# control_board.net
KiCad netlist of a schematic drawn in EAGLE
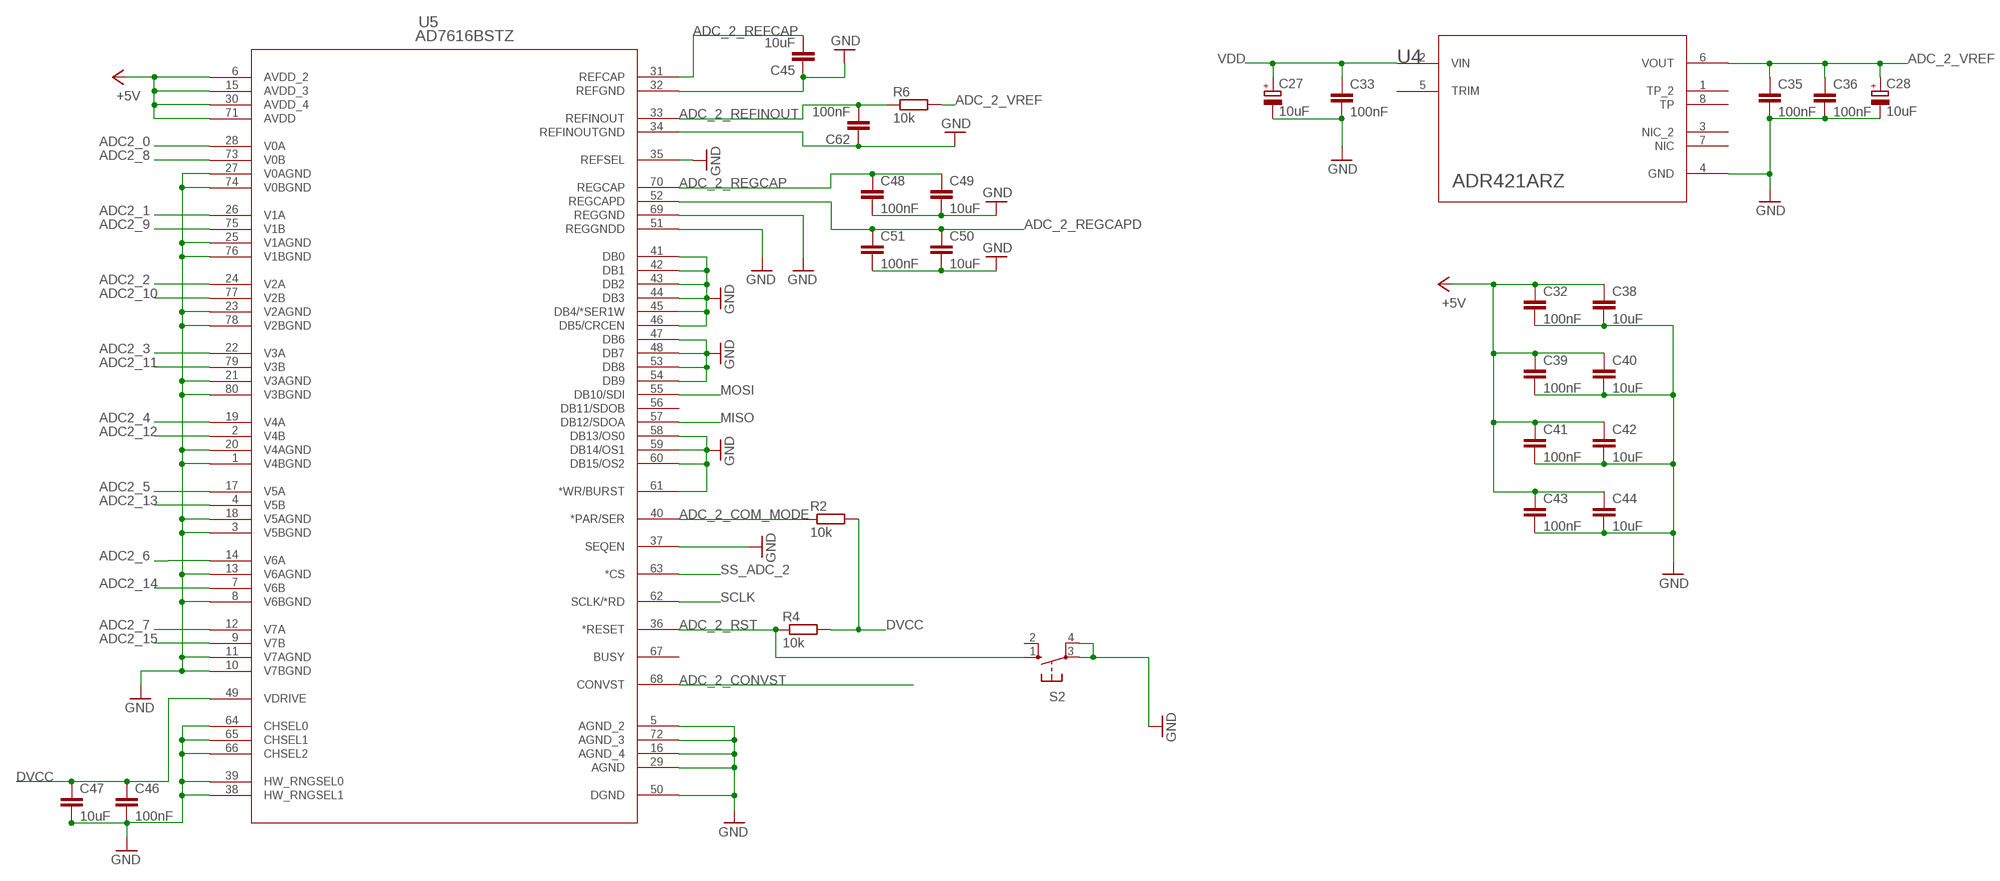
[diagram p0: schematic, sheet 1]
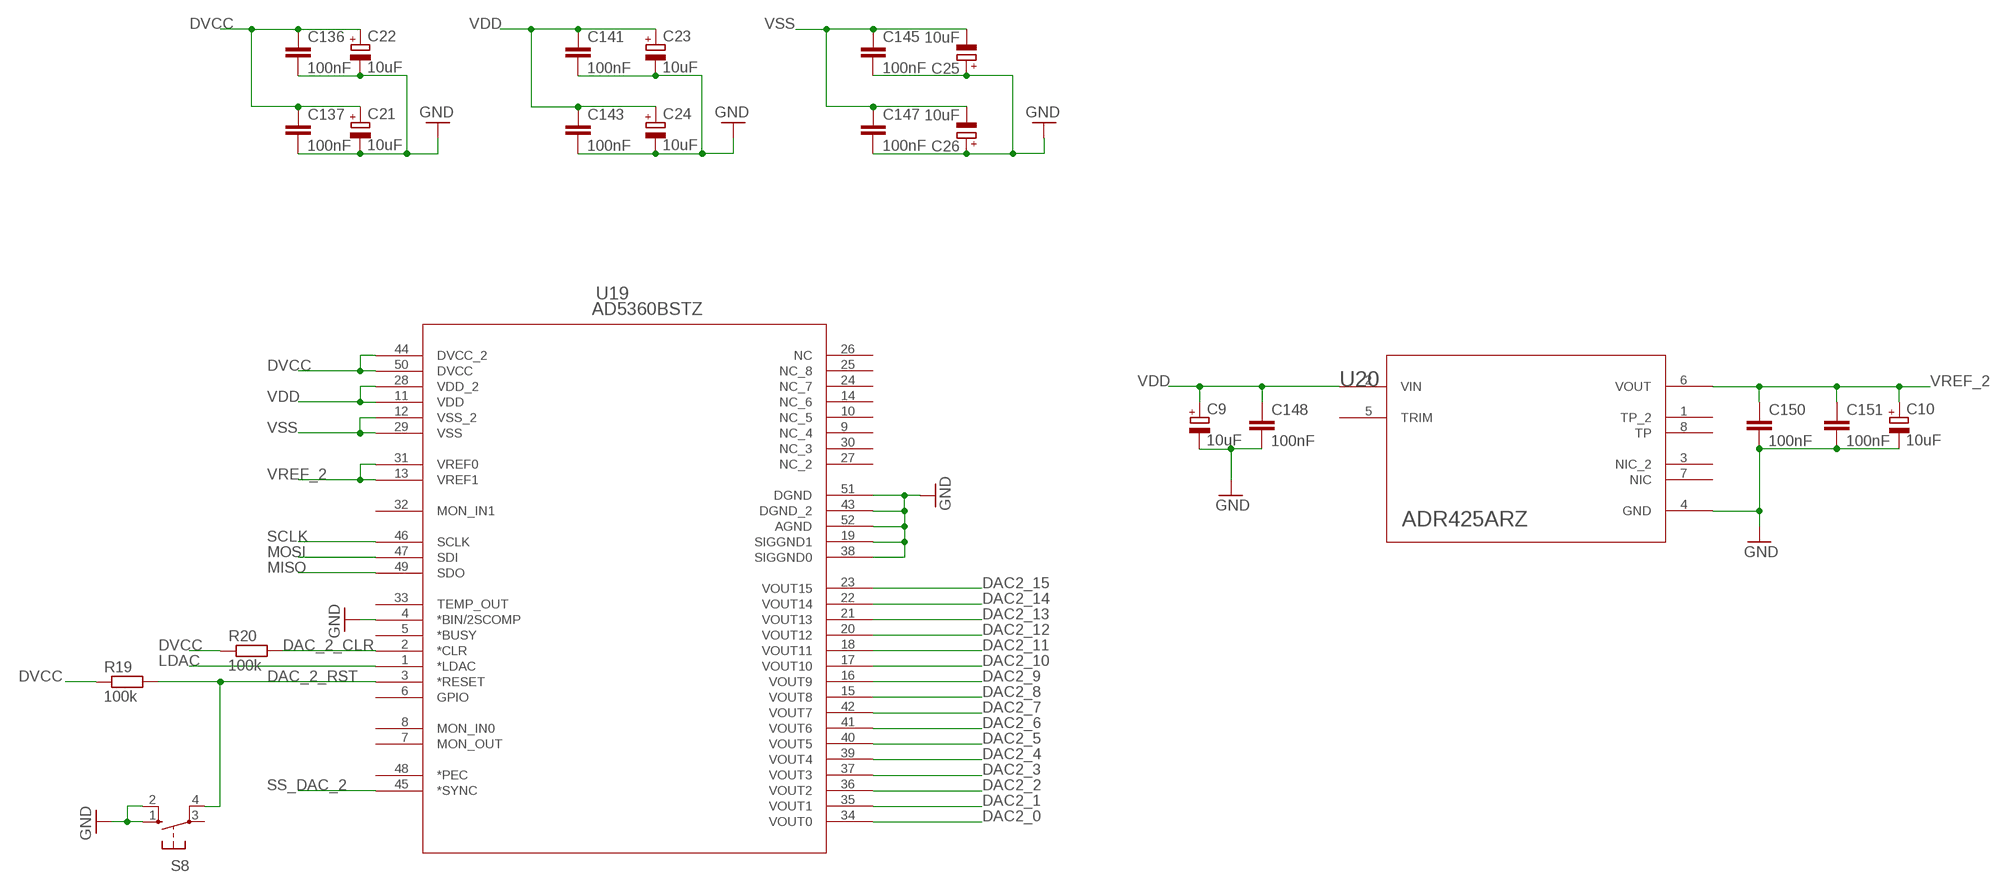
[diagram p1: schematic, sheet 2]
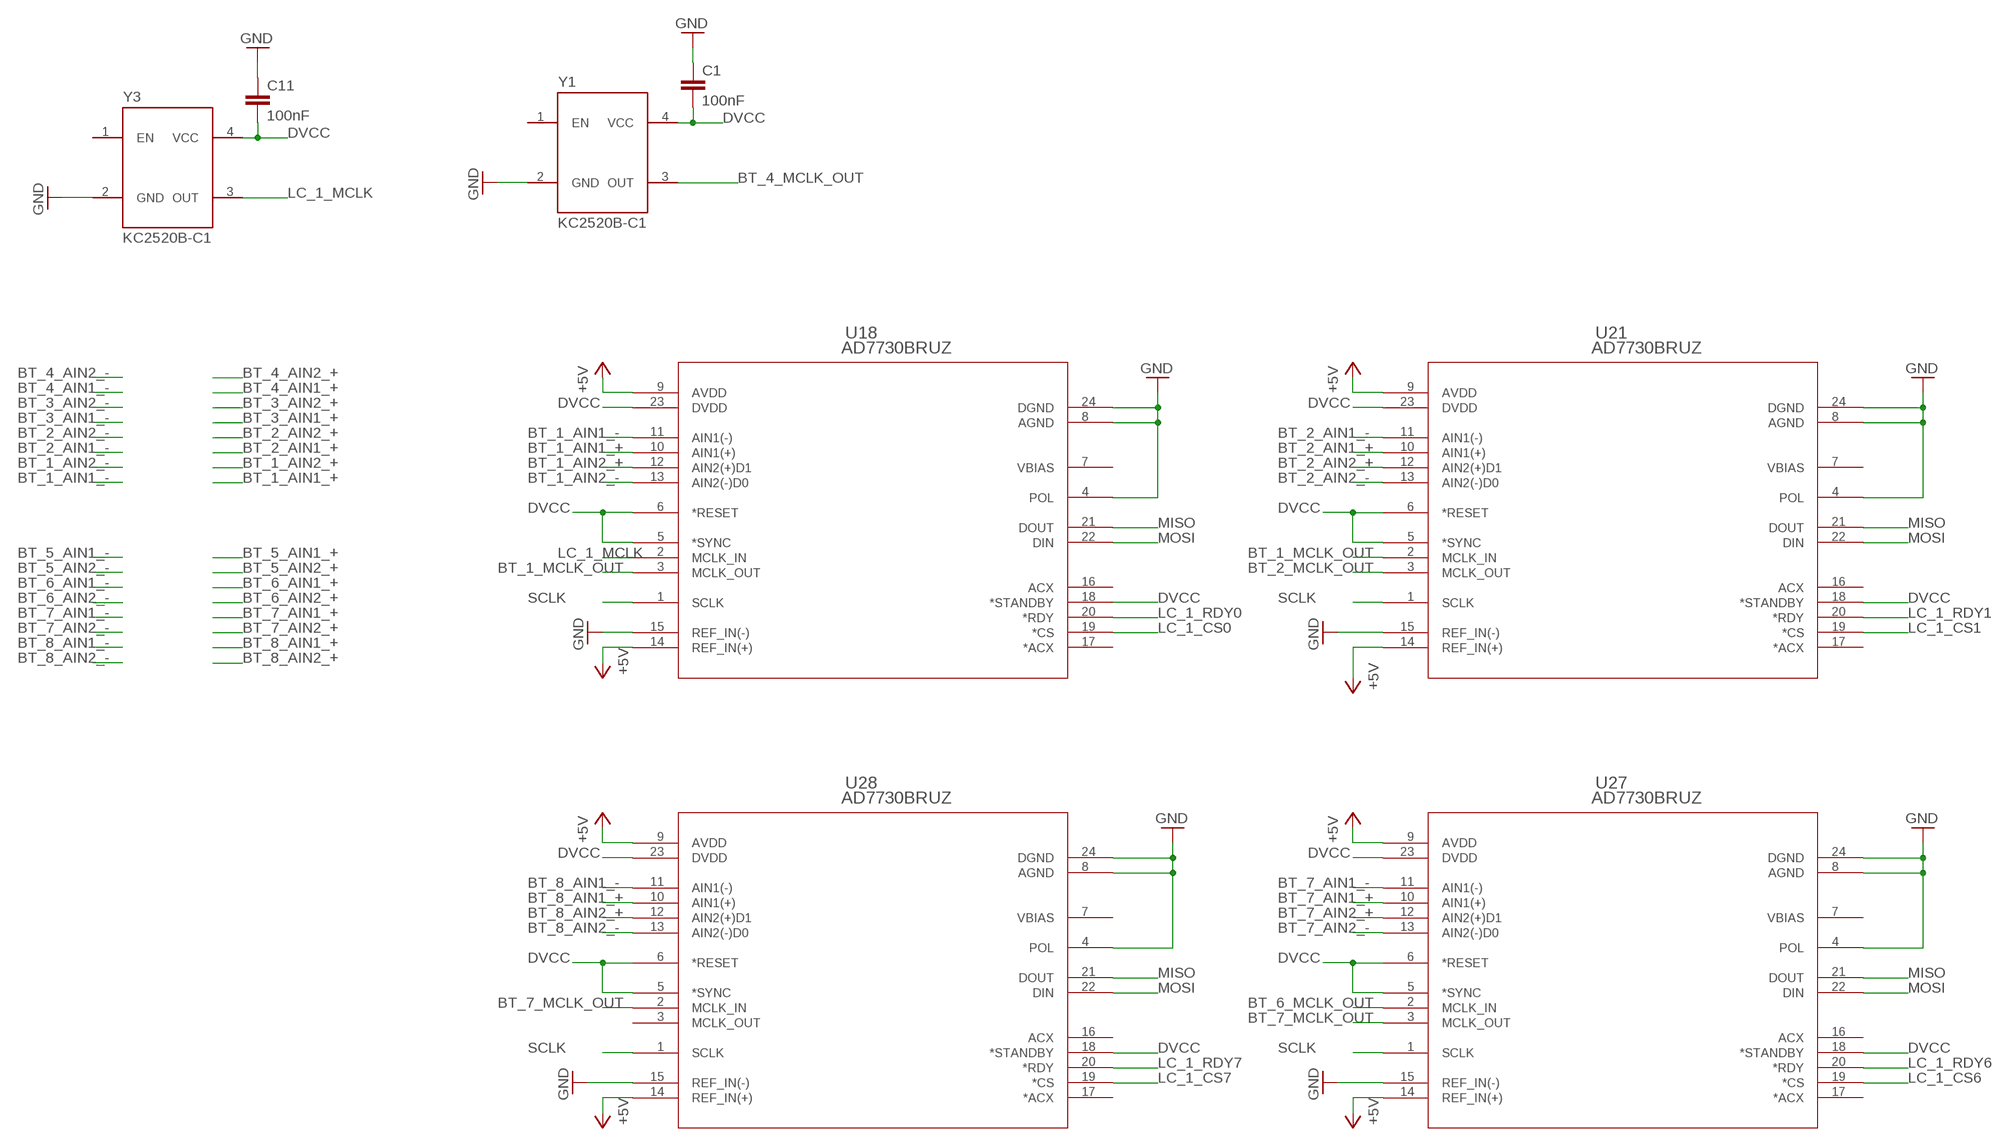
[diagram p2: schematic, sheet 3, part 1 of 2]
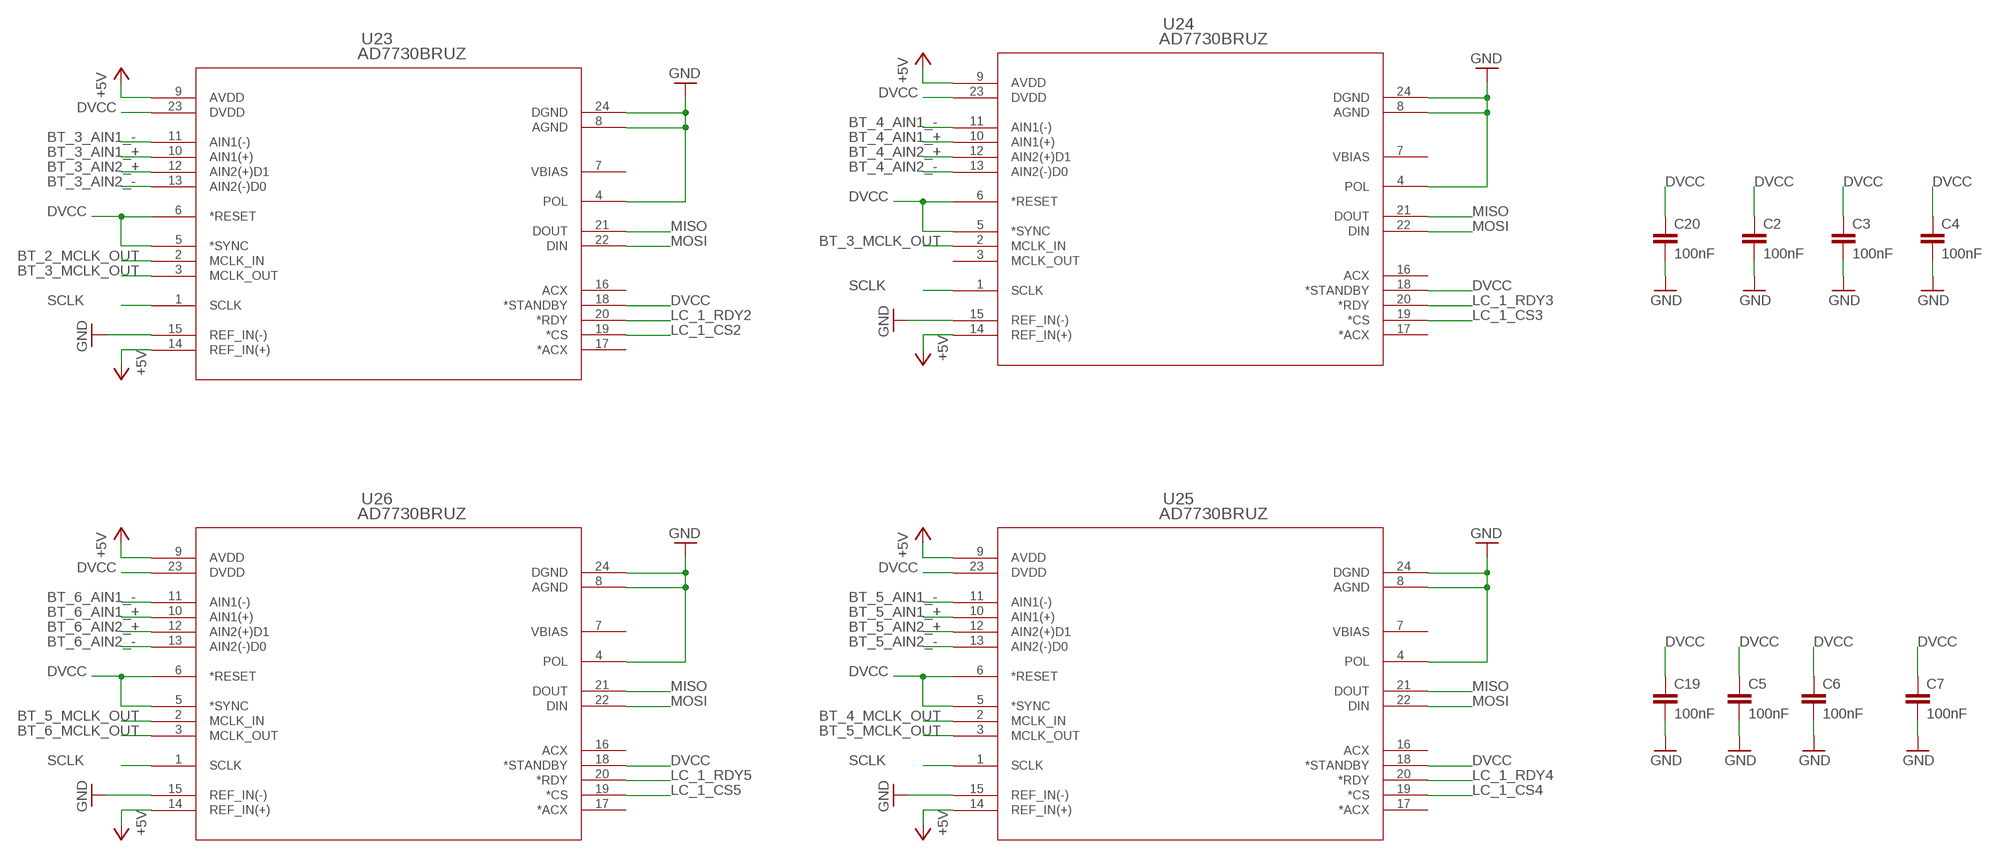
[diagram p3: schematic, sheet 3, part 2 of 2]
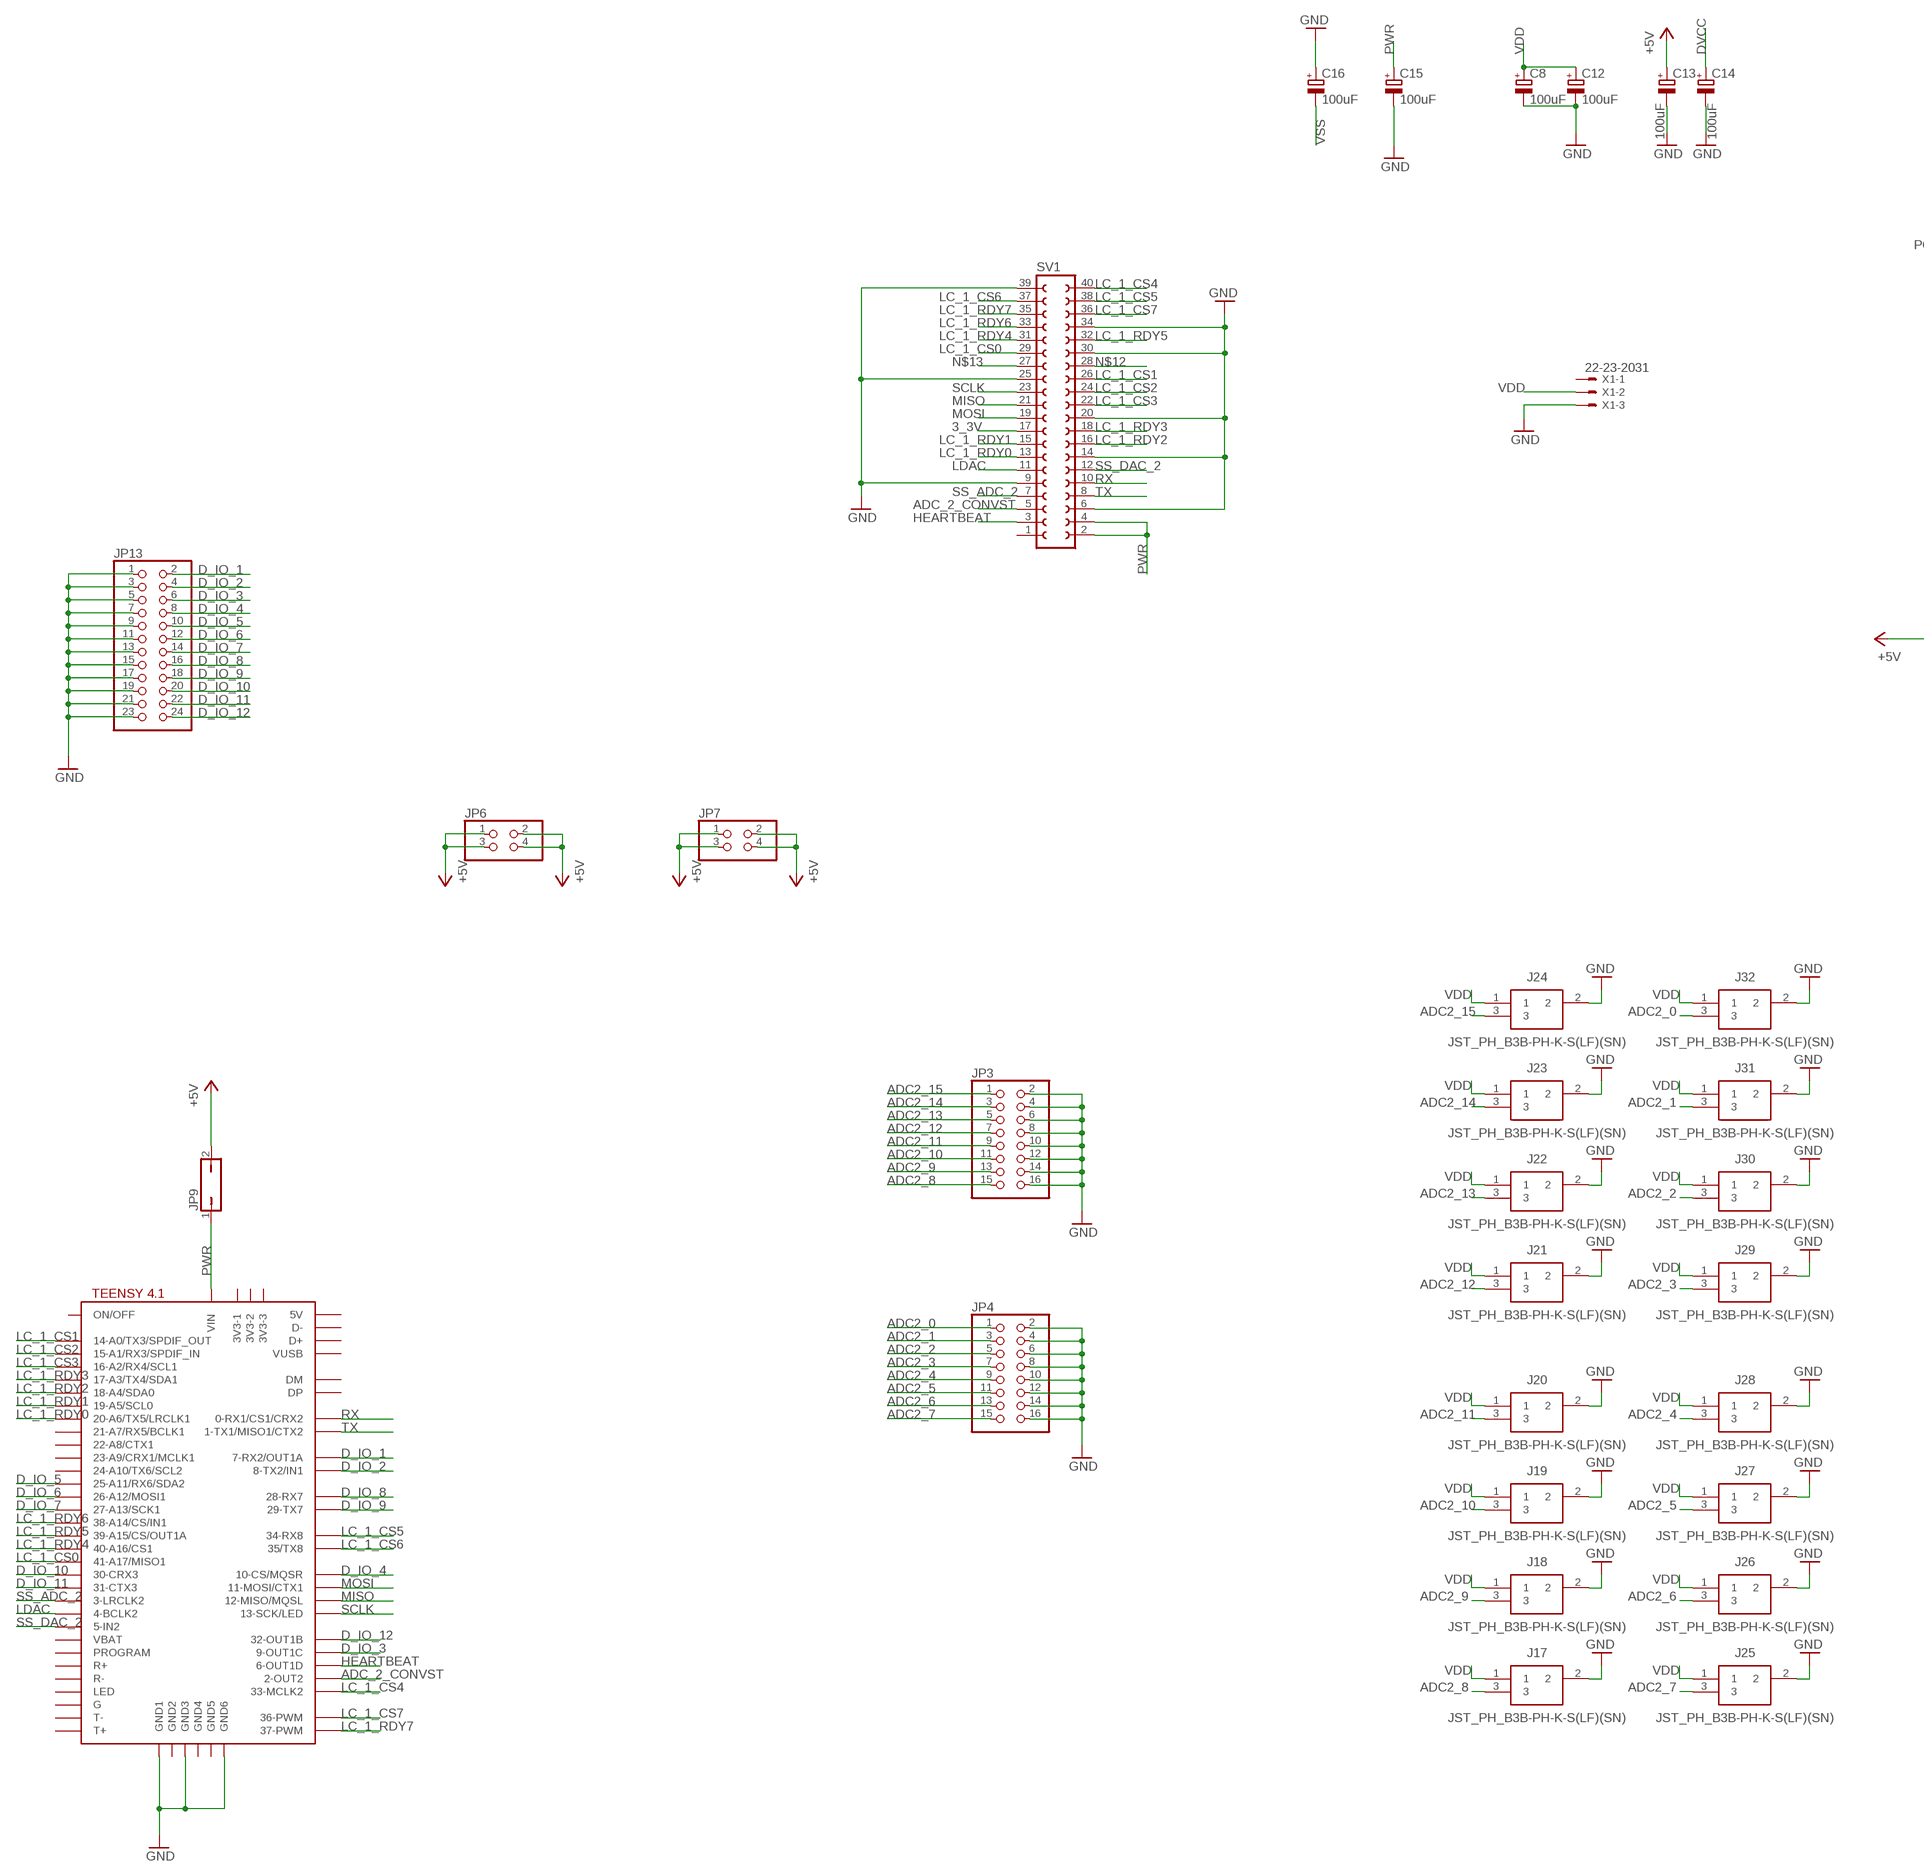
[diagram p4: schematic, sheet 4, part 1 of 2]
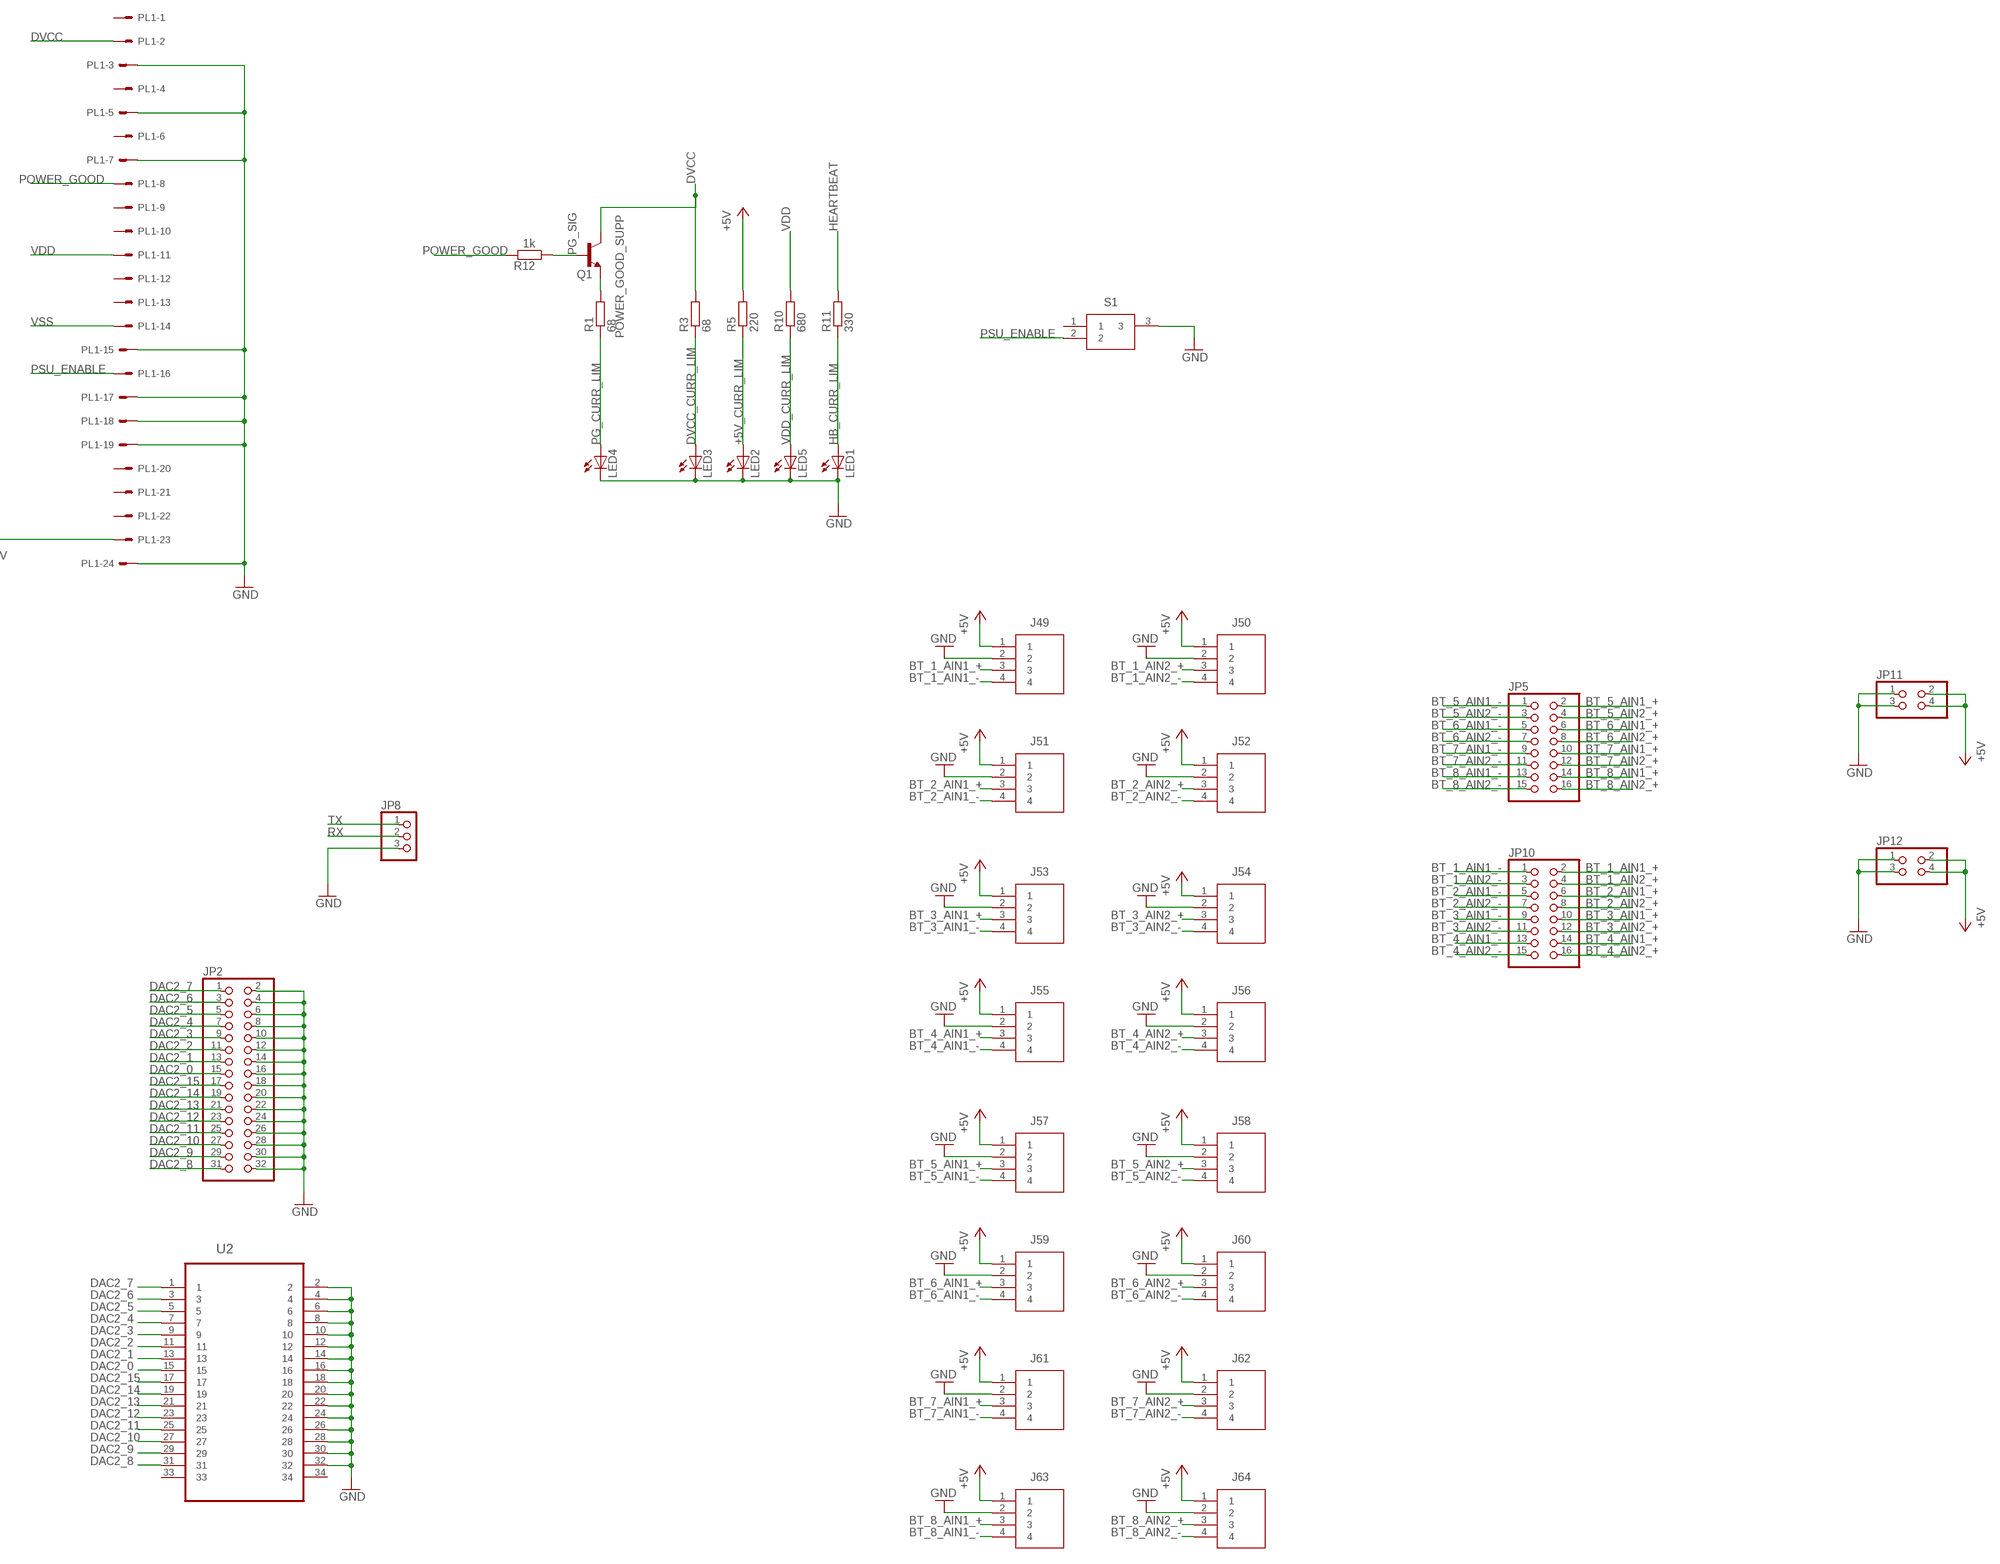
[diagram p5: schematic, sheet 4, part 2 of 2]

(export (version "E")
  (design (tool "Eeschema 10.0.6"))
  (components
    (comp (ref "C27")
      (value "10uF")
      (footprint "eagle-import:SMC_A")
      (libsource (lib "eagle-import") (part "resistor_348_CPOL-EUSMCA"))
    )
    (comp (ref "C28")
      (value "10uF")
      (footprint "eagle-import:SMC_A")
      (libsource (lib "eagle-import") (part "resistor_348_CPOL-EUSMCA"))
    )
    (comp (ref "C32")
      (value "100nF")
      (footprint "eagle-import:C0603")
      (libsource (lib "eagle-import") (part "C-EUC0603"))
    )
    (comp (ref "C33")
      (value "100nF")
      (footprint "eagle-import:C0603")
      (libsource (lib "eagle-import") (part "C-EUC0603"))
    )
    (comp (ref "C35")
      (value "100nF")
      (footprint "eagle-import:C0603")
      (libsource (lib "eagle-import") (part "C-EUC0603"))
    )
    (comp (ref "C36")
      (value "100nF")
      (footprint "eagle-import:C0603")
      (libsource (lib "eagle-import") (part "C-EUC0603"))
    )
    (comp (ref "C38")
      (value "10uF")
      (footprint "eagle-import:C0603")
      (libsource (lib "eagle-import") (part "C-EUC0603"))
    )
    (comp (ref "C39")
      (value "100nF")
      (footprint "eagle-import:C0603")
      (libsource (lib "eagle-import") (part "C-EUC0603"))
    )
    (comp (ref "C40")
      (value "10uF")
      (footprint "eagle-import:C0603")
      (libsource (lib "eagle-import") (part "C-EUC0603"))
    )
    (comp (ref "C41")
      (value "100nF")
      (footprint "eagle-import:C0603")
      (libsource (lib "eagle-import") (part "C-EUC0603"))
    )
    (comp (ref "C42")
      (value "10uF")
      (footprint "eagle-import:C0603")
      (libsource (lib "eagle-import") (part "C-EUC0603"))
    )
    (comp (ref "C43")
      (value "100nF")
      (footprint "eagle-import:C0603")
      (libsource (lib "eagle-import") (part "C-EUC0603"))
    )
    (comp (ref "C44")
      (value "10uF")
      (footprint "eagle-import:C0603")
      (libsource (lib "eagle-import") (part "C-EUC0603"))
    )
    (comp (ref "C45")
      (value "10uF")
      (footprint "eagle-import:C0603")
      (libsource (lib "eagle-import") (part "C-EUC0603"))
    )
    (comp (ref "C46")
      (value "100nF")
      (footprint "eagle-import:C0603")
      (libsource (lib "eagle-import") (part "C-EUC0603"))
    )
    (comp (ref "C47")
      (value "10uF")
      (footprint "eagle-import:C0603")
      (libsource (lib "eagle-import") (part "C-EUC0603"))
    )
    (comp (ref "C48")
      (value "100nF")
      (footprint "eagle-import:C0603")
      (libsource (lib "eagle-import") (part "C-EUC0603"))
    )
    (comp (ref "C49")
      (value "10uF")
      (footprint "eagle-import:C0603")
      (libsource (lib "eagle-import") (part "C-EUC0603"))
    )
    (comp (ref "C50")
      (value "10uF")
      (footprint "eagle-import:C0603")
      (libsource (lib "eagle-import") (part "C-EUC0603"))
    )
    (comp (ref "C51")
      (value "100nF")
      (footprint "eagle-import:C0603")
      (libsource (lib "eagle-import") (part "C-EUC0603"))
    )
    (comp (ref "C62")
      (value "100nF")
      (footprint "eagle-import:C0603")
      (libsource (lib "eagle-import") (part "C-EUC0603"))
    )
    (comp (ref "R2")
      (value "10k")
      (footprint "eagle-import:R0603")
      (libsource (lib "eagle-import") (part "R-EU_R0603"))
    )
    (comp (ref "R4")
      (value "10k")
      (footprint "eagle-import:R0603")
      (libsource (lib "eagle-import") (part "R-EU_R0603"))
    )
    (comp (ref "R6")
      (value "10k")
      (footprint "eagle-import:R0603")
      (libsource (lib "eagle-import") (part "R-EU_R0603"))
    )
    (comp (ref "S2")
      (value "10-XX")
      (footprint "eagle-import:B3F-10XX")
      (fields (field (name "MPN") "B3F-1000"))
      (libsource (lib "eagle-import") (part "10-XX"))
    )
    (comp (ref "U4")
      (value "ADR421ARZ")
      (footprint "eagle-import:R_8")
      (fields (field (name "MANUFACTURER_PART_NUMBER") "ADR423ARZ"))
      (libsource (lib "eagle-import") (part "ADR423ARZ"))
    )
    (comp (ref "U5")
      (value "AD7616BSTZ")
      (footprint "eagle-import:ST_80_2")
      (libsource (lib "eagle-import") (part "AD7616BSTZ"))
    )
    (comp (ref "C9")
      (value "10uF")
      (footprint "eagle-import:SMC_A")
      (libsource (lib "eagle-import") (part "resistor_348_CPOL-EUSMCA"))
    )
    (comp (ref "C10")
      (value "10uF")
      (footprint "eagle-import:SMC_A")
      (libsource (lib "eagle-import") (part "resistor_348_CPOL-EUSMCA"))
    )
    (comp (ref "C21")
      (value "10uF")
      (footprint "eagle-import:SMC_A")
      (libsource (lib "eagle-import") (part "resistor_348_CPOL-EUSMCA"))
    )
    (comp (ref "C22")
      (value "10uF")
      (footprint "eagle-import:SMC_A")
      (libsource (lib "eagle-import") (part "resistor_348_CPOL-EUSMCA"))
    )
    (comp (ref "C23")
      (value "10uF")
      (footprint "eagle-import:SMC_A")
      (libsource (lib "eagle-import") (part "resistor_348_CPOL-EUSMCA"))
    )
    (comp (ref "C24")
      (value "10uF")
      (footprint "eagle-import:SMC_A")
      (libsource (lib "eagle-import") (part "resistor_348_CPOL-EUSMCA"))
    )
    (comp (ref "C25")
      (value "10uF")
      (footprint "eagle-import:SMC_A")
      (libsource (lib "eagle-import") (part "resistor_348_CPOL-EUSMCA"))
    )
    (comp (ref "C26")
      (value "10uF")
      (footprint "eagle-import:SMC_A")
      (libsource (lib "eagle-import") (part "resistor_348_CPOL-EUSMCA"))
    )
    (comp (ref "C136")
      (value "100nF")
      (footprint "eagle-import:C0603")
      (libsource (lib "eagle-import") (part "C-EUC0603"))
    )
    (comp (ref "C137")
      (value "100nF")
      (footprint "eagle-import:C0603")
      (libsource (lib "eagle-import") (part "C-EUC0603"))
    )
    (comp (ref "C141")
      (value "100nF")
      (footprint "eagle-import:C0603")
      (libsource (lib "eagle-import") (part "C-EUC0603"))
    )
    (comp (ref "C143")
      (value "100nF")
      (footprint "eagle-import:C0603")
      (libsource (lib "eagle-import") (part "C-EUC0603"))
    )
    (comp (ref "C145")
      (value "100nF")
      (footprint "eagle-import:C0603")
      (libsource (lib "eagle-import") (part "C-EUC0603"))
    )
    (comp (ref "C147")
      (value "100nF")
      (footprint "eagle-import:C0603")
      (libsource (lib "eagle-import") (part "C-EUC0603"))
    )
    (comp (ref "C148")
      (value "100nF")
      (footprint "eagle-import:C0603")
      (libsource (lib "eagle-import") (part "C-EUC0603"))
    )
    (comp (ref "C150")
      (value "100nF")
      (footprint "eagle-import:C0603")
      (libsource (lib "eagle-import") (part "C-EUC0603"))
    )
    (comp (ref "C151")
      (value "100nF")
      (footprint "eagle-import:C0603")
      (libsource (lib "eagle-import") (part "C-EUC0603"))
    )
    (comp (ref "R19")
      (value "100k")
      (footprint "eagle-import:R0603")
      (libsource (lib "eagle-import") (part "R-EU_R0603"))
    )
    (comp (ref "R20")
      (value "100k")
      (footprint "eagle-import:R0603")
      (libsource (lib "eagle-import") (part "R-EU_R0603"))
    )
    (comp (ref "S8")
      (value "10-XX")
      (footprint "eagle-import:B3F-10XX")
      (fields (field (name "MPN") "B3F-1000"))
      (libsource (lib "eagle-import") (part "10-XX"))
    )
    (comp (ref "U19")
      (value "AD5360BSTZ")
      (footprint "eagle-import:ST_52")
      (libsource (lib "eagle-import") (part "AD5360BSTZ"))
    )
    (comp (ref "U20")
      (value "ADR425ARZ")
      (footprint "eagle-import:R_8")
      (fields (field (name "MANUFACTURER_PART_NUMBER") "ADR423ARZ"))
      (libsource (lib "eagle-import") (part "ADR423ARZ"))
    )
    (comp (ref "C1")
      (value "100nF")
      (footprint "eagle-import:C0603")
      (libsource (lib "eagle-import") (part "C-EUC0603"))
    )
    (comp (ref "C2")
      (value "100nF")
      (footprint "eagle-import:C0603")
      (libsource (lib "eagle-import") (part "C-EUC0603"))
    )
    (comp (ref "C3")
      (value "100nF")
      (footprint "eagle-import:C0603")
      (libsource (lib "eagle-import") (part "C-EUC0603"))
    )
    (comp (ref "C4")
      (value "100nF")
      (footprint "eagle-import:C0603")
      (libsource (lib "eagle-import") (part "C-EUC0603"))
    )
    (comp (ref "C5")
      (value "100nF")
      (footprint "eagle-import:C0603")
      (libsource (lib "eagle-import") (part "C-EUC0603"))
    )
    (comp (ref "C6")
      (value "100nF")
      (footprint "eagle-import:C0603")
      (libsource (lib "eagle-import") (part "C-EUC0603"))
    )
    (comp (ref "C7")
      (value "100nF")
      (footprint "eagle-import:C0603")
      (libsource (lib "eagle-import") (part "C-EUC0603"))
    )
    (comp (ref "C11")
      (value "100nF")
      (footprint "eagle-import:C0603")
      (libsource (lib "eagle-import") (part "C-EUC0603"))
    )
    (comp (ref "C19")
      (value "100nF")
      (footprint "eagle-import:C0603")
      (libsource (lib "eagle-import") (part "C-EUC0603"))
    )
    (comp (ref "C20")
      (value "100nF")
      (footprint "eagle-import:C0603")
      (libsource (lib "eagle-import") (part "C-EUC0603"))
    )
    (comp (ref "U18")
      (value "AD7730BRUZ")
      (footprint "eagle-import:RU_24")
      (libsource (lib "eagle-import") (part "AD7730BRUZ"))
    )
    (comp (ref "U21")
      (value "AD7730BRUZ")
      (footprint "eagle-import:RU_24")
      (libsource (lib "eagle-import") (part "AD7730BRUZ"))
    )
    (comp (ref "U23")
      (value "AD7730BRUZ")
      (footprint "eagle-import:RU_24")
      (libsource (lib "eagle-import") (part "AD7730BRUZ"))
    )
    (comp (ref "U24")
      (value "AD7730BRUZ")
      (footprint "eagle-import:RU_24")
      (libsource (lib "eagle-import") (part "AD7730BRUZ"))
    )
    (comp (ref "U25")
      (value "AD7730BRUZ")
      (footprint "eagle-import:RU_24")
      (libsource (lib "eagle-import") (part "AD7730BRUZ"))
    )
    (comp (ref "U26")
      (value "AD7730BRUZ")
      (footprint "eagle-import:RU_24")
      (libsource (lib "eagle-import") (part "AD7730BRUZ"))
    )
    (comp (ref "U27")
      (value "AD7730BRUZ")
      (footprint "eagle-import:RU_24")
      (libsource (lib "eagle-import") (part "AD7730BRUZ"))
    )
    (comp (ref "U28")
      (value "AD7730BRUZ")
      (footprint "eagle-import:RU_24")
      (libsource (lib "eagle-import") (part "AD7730BRUZ"))
    )
    (comp (ref "Y1")
      (value "KC2520B-C1")
      (footprint "eagle-import:KC2520B-C1")
      (libsource (lib "eagle-import") (part "KC2520B-C1"))
    )
    (comp (ref "Y3")
      (value "KC2520B-C1")
      (footprint "eagle-import:KC2520B-C1")
      (libsource (lib "eagle-import") (part "KC2520B-C1"))
    )
    (comp (ref "C8")
      (value "100uF")
      (footprint "eagle-import:E3,5-8")
      (libsource (lib "eagle-import") (part "CPOL-EUE3.5-8"))
    )
    (comp (ref "C12")
      (value "100uF")
      (footprint "eagle-import:E3,5-8")
      (libsource (lib "eagle-import") (part "CPOL-EUE3.5-8"))
    )
    (comp (ref "C13")
      (value "100uF")
      (footprint "eagle-import:E3,5-8")
      (libsource (lib "eagle-import") (part "CPOL-EUE3.5-8"))
    )
    (comp (ref "C14")
      (value "100uF")
      (footprint "eagle-import:E3,5-8")
      (libsource (lib "eagle-import") (part "CPOL-EUE3.5-8"))
    )
    (comp (ref "C15")
      (value "100uF")
      (footprint "eagle-import:E3,5-8")
      (libsource (lib "eagle-import") (part "CPOL-EUE3.5-8"))
    )
    (comp (ref "C16")
      (value "100uF")
      (footprint "eagle-import:E3,5-8")
      (libsource (lib "eagle-import") (part "CPOL-EUE3.5-8"))
    )
    (comp (ref "J17")
      (value "JST_PH_B3B-PH-K-S(LF)(SN)")
      (footprint "eagle-import:JST_PH_SHDR3W50P0X200_1X3_790X450X600")
      (fields
        (field (name "MANUFACTURER_PART_NUMBER") "B3B-PH-K-S(LF)(SN)")
        (field (name "RS_PART_NUMBER") "8201431P")
      )
      (libsource (lib "eagle-import") (part "JST_PH_B3B-PH-K-S(LF)(SN)"))
    )
    (comp (ref "J18")
      (value "JST_PH_B3B-PH-K-S(LF)(SN)")
      (footprint "eagle-import:JST_PH_SHDR3W50P0X200_1X3_790X450X600")
      (fields
        (field (name "MANUFACTURER_PART_NUMBER") "B3B-PH-K-S(LF)(SN)")
        (field (name "RS_PART_NUMBER") "8201431P")
      )
      (libsource (lib "eagle-import") (part "JST_PH_B3B-PH-K-S(LF)(SN)"))
    )
    (comp (ref "J19")
      (value "JST_PH_B3B-PH-K-S(LF)(SN)")
      (footprint "eagle-import:JST_PH_SHDR3W50P0X200_1X3_790X450X600")
      (fields
        (field (name "MANUFACTURER_PART_NUMBER") "B3B-PH-K-S(LF)(SN)")
        (field (name "RS_PART_NUMBER") "8201431P")
      )
      (libsource (lib "eagle-import") (part "JST_PH_B3B-PH-K-S(LF)(SN)"))
    )
    (comp (ref "J20")
      (value "JST_PH_B3B-PH-K-S(LF)(SN)")
      (footprint "eagle-import:JST_PH_SHDR3W50P0X200_1X3_790X450X600")
      (fields
        (field (name "MANUFACTURER_PART_NUMBER") "B3B-PH-K-S(LF)(SN)")
        (field (name "RS_PART_NUMBER") "8201431P")
      )
      (libsource (lib "eagle-import") (part "JST_PH_B3B-PH-K-S(LF)(SN)"))
    )
    (comp (ref "J21")
      (value "JST_PH_B3B-PH-K-S(LF)(SN)")
      (footprint "eagle-import:JST_PH_SHDR3W50P0X200_1X3_790X450X600")
      (fields
        (field (name "MANUFACTURER_PART_NUMBER") "B3B-PH-K-S(LF)(SN)")
        (field (name "RS_PART_NUMBER") "8201431P")
      )
      (libsource (lib "eagle-import") (part "JST_PH_B3B-PH-K-S(LF)(SN)"))
    )
    (comp (ref "J22")
      (value "JST_PH_B3B-PH-K-S(LF)(SN)")
      (footprint "eagle-import:JST_PH_SHDR3W50P0X200_1X3_790X450X600")
      (fields
        (field (name "MANUFACTURER_PART_NUMBER") "B3B-PH-K-S(LF)(SN)")
        (field (name "RS_PART_NUMBER") "8201431P")
      )
      (libsource (lib "eagle-import") (part "JST_PH_B3B-PH-K-S(LF)(SN)"))
    )
    (comp (ref "J23")
      (value "JST_PH_B3B-PH-K-S(LF)(SN)")
      (footprint "eagle-import:JST_PH_SHDR3W50P0X200_1X3_790X450X600")
      (fields
        (field (name "MANUFACTURER_PART_NUMBER") "B3B-PH-K-S(LF)(SN)")
        (field (name "RS_PART_NUMBER") "8201431P")
      )
      (libsource (lib "eagle-import") (part "JST_PH_B3B-PH-K-S(LF)(SN)"))
    )
    (comp (ref "J24")
      (value "JST_PH_B3B-PH-K-S(LF)(SN)")
      (footprint "eagle-import:JST_PH_SHDR3W50P0X200_1X3_790X450X600")
      (fields
        (field (name "MANUFACTURER_PART_NUMBER") "B3B-PH-K-S(LF)(SN)")
        (field (name "RS_PART_NUMBER") "8201431P")
      )
      (libsource (lib "eagle-import") (part "JST_PH_B3B-PH-K-S(LF)(SN)"))
    )
    (comp (ref "J25")
      (value "JST_PH_B3B-PH-K-S(LF)(SN)")
      (footprint "eagle-import:JST_PH_SHDR3W50P0X200_1X3_790X450X600")
      (fields
        (field (name "MANUFACTURER_PART_NUMBER") "B3B-PH-K-S(LF)(SN)")
        (field (name "RS_PART_NUMBER") "8201431P")
      )
      (libsource (lib "eagle-import") (part "JST_PH_B3B-PH-K-S(LF)(SN)"))
    )
    (comp (ref "J26")
      (value "JST_PH_B3B-PH-K-S(LF)(SN)")
      (footprint "eagle-import:JST_PH_SHDR3W50P0X200_1X3_790X450X600")
      (fields
        (field (name "MANUFACTURER_PART_NUMBER") "B3B-PH-K-S(LF)(SN)")
        (field (name "RS_PART_NUMBER") "8201431P")
      )
      (libsource (lib "eagle-import") (part "JST_PH_B3B-PH-K-S(LF)(SN)"))
    )
    (comp (ref "J27")
      (value "JST_PH_B3B-PH-K-S(LF)(SN)")
      (footprint "eagle-import:JST_PH_SHDR3W50P0X200_1X3_790X450X600")
      (fields
        (field (name "MANUFACTURER_PART_NUMBER") "B3B-PH-K-S(LF)(SN)")
        (field (name "RS_PART_NUMBER") "8201431P")
      )
      (libsource (lib "eagle-import") (part "JST_PH_B3B-PH-K-S(LF)(SN)"))
    )
    (comp (ref "J28")
      (value "JST_PH_B3B-PH-K-S(LF)(SN)")
      (footprint "eagle-import:JST_PH_SHDR3W50P0X200_1X3_790X450X600")
      (fields
        (field (name "MANUFACTURER_PART_NUMBER") "B3B-PH-K-S(LF)(SN)")
        (field (name "RS_PART_NUMBER") "8201431P")
      )
      (libsource (lib "eagle-import") (part "JST_PH_B3B-PH-K-S(LF)(SN)"))
    )
    (comp (ref "J29")
      (value "JST_PH_B3B-PH-K-S(LF)(SN)")
      (footprint "eagle-import:JST_PH_SHDR3W50P0X200_1X3_790X450X600")
      (fields
        (field (name "MANUFACTURER_PART_NUMBER") "B3B-PH-K-S(LF)(SN)")
        (field (name "RS_PART_NUMBER") "8201431P")
      )
      (libsource (lib "eagle-import") (part "JST_PH_B3B-PH-K-S(LF)(SN)"))
    )
    (comp (ref "J30")
      (value "JST_PH_B3B-PH-K-S(LF)(SN)")
      (footprint "eagle-import:JST_PH_SHDR3W50P0X200_1X3_790X450X600")
      (fields
        (field (name "MANUFACTURER_PART_NUMBER") "B3B-PH-K-S(LF)(SN)")
        (field (name "RS_PART_NUMBER") "8201431P")
      )
      (libsource (lib "eagle-import") (part "JST_PH_B3B-PH-K-S(LF)(SN)"))
    )
    (comp (ref "J31")
      (value "JST_PH_B3B-PH-K-S(LF)(SN)")
      (footprint "eagle-import:JST_PH_SHDR3W50P0X200_1X3_790X450X600")
      (fields
        (field (name "MANUFACTURER_PART_NUMBER") "B3B-PH-K-S(LF)(SN)")
        (field (name "RS_PART_NUMBER") "8201431P")
      )
      (libsource (lib "eagle-import") (part "JST_PH_B3B-PH-K-S(LF)(SN)"))
    )
    (comp (ref "J32")
      (value "JST_PH_B3B-PH-K-S(LF)(SN)")
      (footprint "eagle-import:JST_PH_SHDR3W50P0X200_1X3_790X450X600")
      (fields
        (field (name "MANUFACTURER_PART_NUMBER") "B3B-PH-K-S(LF)(SN)")
        (field (name "RS_PART_NUMBER") "8201431P")
      )
      (libsource (lib "eagle-import") (part "JST_PH_B3B-PH-K-S(LF)(SN)"))
    )
    (comp (ref "J49")
      (value "B4B-PH-K-S(LF)(SN)")
      (footprint "eagle-import:SHDR4W50P0X200_1X4_990X450X600")
      (fields (field (name "RS_PART_NUMBER") "8201434P"))
      (libsource (lib "eagle-import") (part "B4B-PH-K-S(LF)(SN)"))
    )
    (comp (ref "J50")
      (value "B4B-PH-K-S(LF)(SN)")
      (footprint "eagle-import:SHDR4W50P0X200_1X4_990X450X600")
      (fields (field (name "RS_PART_NUMBER") "8201434P"))
      (libsource (lib "eagle-import") (part "B4B-PH-K-S(LF)(SN)"))
    )
    (comp (ref "J51")
      (value "B4B-PH-K-S(LF)(SN)")
      (footprint "eagle-import:SHDR4W50P0X200_1X4_990X450X600")
      (fields (field (name "RS_PART_NUMBER") "8201434P"))
      (libsource (lib "eagle-import") (part "B4B-PH-K-S(LF)(SN)"))
    )
    (comp (ref "J52")
      (value "B4B-PH-K-S(LF)(SN)")
      (footprint "eagle-import:SHDR4W50P0X200_1X4_990X450X600")
      (fields (field (name "RS_PART_NUMBER") "8201434P"))
      (libsource (lib "eagle-import") (part "B4B-PH-K-S(LF)(SN)"))
    )
    (comp (ref "J53")
      (value "B4B-PH-K-S(LF)(SN)")
      (footprint "eagle-import:SHDR4W50P0X200_1X4_990X450X600")
      (fields (field (name "RS_PART_NUMBER") "8201434P"))
      (libsource (lib "eagle-import") (part "B4B-PH-K-S(LF)(SN)"))
    )
    (comp (ref "J54")
      (value "B4B-PH-K-S(LF)(SN)")
      (footprint "eagle-import:SHDR4W50P0X200_1X4_990X450X600")
      (fields (field (name "RS_PART_NUMBER") "8201434P"))
      (libsource (lib "eagle-import") (part "B4B-PH-K-S(LF)(SN)"))
    )
    (comp (ref "J55")
      (value "B4B-PH-K-S(LF)(SN)")
      (footprint "eagle-import:SHDR4W50P0X200_1X4_990X450X600")
      (fields (field (name "RS_PART_NUMBER") "8201434P"))
      (libsource (lib "eagle-import") (part "B4B-PH-K-S(LF)(SN)"))
    )
    (comp (ref "J56")
      (value "B4B-PH-K-S(LF)(SN)")
      (footprint "eagle-import:SHDR4W50P0X200_1X4_990X450X600")
      (fields (field (name "RS_PART_NUMBER") "8201434P"))
      (libsource (lib "eagle-import") (part "B4B-PH-K-S(LF)(SN)"))
    )
    (comp (ref "J57")
      (value "B4B-PH-K-S(LF)(SN)")
      (footprint "eagle-import:SHDR4W50P0X200_1X4_990X450X600")
      (fields (field (name "RS_PART_NUMBER") "8201434P"))
      (libsource (lib "eagle-import") (part "B4B-PH-K-S(LF)(SN)"))
    )
    (comp (ref "J58")
      (value "B4B-PH-K-S(LF)(SN)")
      (footprint "eagle-import:SHDR4W50P0X200_1X4_990X450X600")
      (fields (field (name "RS_PART_NUMBER") "8201434P"))
      (libsource (lib "eagle-import") (part "B4B-PH-K-S(LF)(SN)"))
    )
    (comp (ref "J59")
      (value "B4B-PH-K-S(LF)(SN)")
      (footprint "eagle-import:SHDR4W50P0X200_1X4_990X450X600")
      (fields (field (name "RS_PART_NUMBER") "8201434P"))
      (libsource (lib "eagle-import") (part "B4B-PH-K-S(LF)(SN)"))
    )
    (comp (ref "J60")
      (value "B4B-PH-K-S(LF)(SN)")
      (footprint "eagle-import:SHDR4W50P0X200_1X4_990X450X600")
      (fields (field (name "RS_PART_NUMBER") "8201434P"))
      (libsource (lib "eagle-import") (part "B4B-PH-K-S(LF)(SN)"))
    )
    (comp (ref "J61")
      (value "B4B-PH-K-S(LF)(SN)")
      (footprint "eagle-import:SHDR4W50P0X200_1X4_990X450X600")
      (fields (field (name "RS_PART_NUMBER") "8201434P"))
      (libsource (lib "eagle-import") (part "B4B-PH-K-S(LF)(SN)"))
    )
    (comp (ref "J62")
      (value "B4B-PH-K-S(LF)(SN)")
      (footprint "eagle-import:SHDR4W50P0X200_1X4_990X450X600")
      (fields (field (name "RS_PART_NUMBER") "8201434P"))
      (libsource (lib "eagle-import") (part "B4B-PH-K-S(LF)(SN)"))
    )
    (comp (ref "J63")
      (value "B4B-PH-K-S(LF)(SN)")
      (footprint "eagle-import:SHDR4W50P0X200_1X4_990X450X600")
      (fields (field (name "RS_PART_NUMBER") "8201434P"))
      (libsource (lib "eagle-import") (part "B4B-PH-K-S(LF)(SN)"))
    )
    (comp (ref "J64")
      (value "B4B-PH-K-S(LF)(SN)")
      (footprint "eagle-import:SHDR4W50P0X200_1X4_990X450X600")
      (fields (field (name "RS_PART_NUMBER") "8201434P"))
      (libsource (lib "eagle-import") (part "B4B-PH-K-S(LF)(SN)"))
    )
    (comp (ref "JP2")
      (value "PINHD-2X16/90")
      (footprint "eagle-import:2X16_90")
      (libsource (lib "eagle-import") (part "PINHD-2X16/90"))
    )
    (comp (ref "JP3")
      (value "PINHD-2X8/90")
      (footprint "eagle-import:2X08_90")
      (libsource (lib "eagle-import") (part "PINHD-2X8/90"))
    )
    (comp (ref "JP4")
      (value "PINHD-2X8/90")
      (footprint "eagle-import:2X08_90")
      (libsource (lib "eagle-import") (part "PINHD-2X8/90"))
    )
    (comp (ref "JP5")
      (value "PINHD-2X8")
      (footprint "eagle-import:2X08")
      (libsource (lib "eagle-import") (part "PINHD-2X8"))
    )
    (comp (ref "JP6")
      (value "PINHD-2X2/90")
      (footprint "eagle-import:2X02_90")
      (libsource (lib "eagle-import") (part "PINHD-2X2/90"))
    )
    (comp (ref "JP7")
      (value "PINHD-2X2/90")
      (footprint "eagle-import:2X02_90")
      (libsource (lib "eagle-import") (part "PINHD-2X2/90"))
    )
    (comp (ref "JP8")
      (value "PINHD-1X3")
      (footprint "eagle-import:1X03")
      (libsource (lib "eagle-import") (part "PINHD-1X3"))
    )
    (comp (ref "JP9")
      (value "JP1Q")
      (footprint "eagle-import:JP1")
      (libsource (lib "eagle-import") (part "JP1Q"))
    )
    (comp (ref "JP10")
      (value "PINHD-2X8")
      (footprint "eagle-import:2X08")
      (libsource (lib "eagle-import") (part "PINHD-2X8"))
    )
    (comp (ref "JP11")
      (value "PINHD-2X2")
      (footprint "eagle-import:2X02")
      (libsource (lib "eagle-import") (part "PINHD-2X2"))
    )
    (comp (ref "JP12")
      (value "PINHD-2X2")
      (footprint "eagle-import:2X02")
      (libsource (lib "eagle-import") (part "PINHD-2X2"))
    )
    (comp (ref "JP13")
      (value "PINHD-2X12_2.54-SMD")
      (footprint "eagle-import:2X12SMD")
      (libsource (lib "eagle-import") (part "PINHD-2X12_2.54-SMD"))
    )
    (comp (ref "LED1")
      (value "LEDCHIP-LED0603")
      (footprint "eagle-import:CHIP-LED0603")
      (libsource (lib "eagle-import") (part "LEDCHIP-LED0603"))
    )
    (comp (ref "LED2")
      (value "LEDCHIP-LED0603")
      (footprint "eagle-import:CHIP-LED0603")
      (libsource (lib "eagle-import") (part "LEDCHIP-LED0603"))
    )
    (comp (ref "LED3")
      (value "LEDCHIP-LED0603")
      (footprint "eagle-import:CHIP-LED0603")
      (libsource (lib "eagle-import") (part "LEDCHIP-LED0603"))
    )
    (comp (ref "LED4")
      (value "LEDCHIP-LED0603")
      (footprint "eagle-import:CHIP-LED0603")
      (libsource (lib "eagle-import") (part "LEDCHIP-LED0603"))
    )
    (comp (ref "LED5")
      (value "LEDCHIP-LED0603")
      (footprint "eagle-import:CHIP-LED0603")
      (libsource (lib "eagle-import") (part "LEDCHIP-LED0603"))
    )
    (comp (ref "PL1")
      (value "555X-24V")
      (footprint "eagle-import:5566-24")
      (libsource (lib "eagle-import") (part "555X-24V"))
    )
    (comp (ref "Q1")
      (value "BCF29SMD")
      (footprint "eagle-import:SOT23-BEC")
      (libsource (lib "eagle-import") (part "BCF29SMD"))
    )
    (comp (ref "R1")
      (value "68")
      (footprint "eagle-import:R0805")
      (libsource (lib "eagle-import") (part "resistor_348_R-EU_R0805"))
    )
    (comp (ref "R3")
      (value "68")
      (footprint "eagle-import:R0805")
      (libsource (lib "eagle-import") (part "resistor_348_R-EU_R0805"))
    )
    (comp (ref "R5")
      (value "220")
      (footprint "eagle-import:R0805")
      (libsource (lib "eagle-import") (part "resistor_348_R-EU_R0805"))
    )
    (comp (ref "R10")
      (value "680")
      (footprint "eagle-import:R0805")
      (libsource (lib "eagle-import") (part "resistor_348_R-EU_R0805"))
    )
    (comp (ref "R11")
      (value "330")
      (footprint "eagle-import:R0805")
      (libsource (lib "eagle-import") (part "resistor_348_R-EU_R0805"))
    )
    (comp (ref "R12")
      (value "1k")
      (footprint "eagle-import:R0805")
      (libsource (lib "eagle-import") (part "resistor_348_R-EU_R0805"))
    )
    (comp (ref "S1")
      (value "1MS1T1B1M2QES-5")
      (footprint "eagle-import:1MS1T1B1M2QES-5")
      (fields (field (name "RS_PART_NUMBER") "7347066P"))
      (libsource (lib "eagle-import") (part "1MS1T1B1M2QES-5"))
    )
    (comp (ref "SV1")
      (value "FE20-2")
      (footprint "eagle-import:FE20-2")
      (libsource (lib "eagle-import") (part "FE20-2"))
    )
    (comp (ref "U$1")
      (value "TEENSY41")
      (footprint "eagle-import:TEENSY41")
      (libsource (lib "eagle-import") (part "TEENSY41"))
    )
    (comp (ref "U2")
      (value "AMP-5103309-7-34PIN_5103309-7")
      (footprint "eagle-import:AMP-5103309-7-34PIN_TYCO_5103309-7")
      (fields (field (name "MPN") "5103309-7"))
      (libsource (lib "eagle-import") (part "AMP-5103309-7-34PIN_5103309-7"))
    )
    (comp (ref "X1")
      (value "22-23-2031")
      (footprint "eagle-import:22-23-2031")
      (fields (field (name "MF") "MOLEX"))
      (libsource (lib "eagle-import") (part "22-23-2031"))
    )
  )
  (nets
    (net (code "1") (name "+5V") (class "Default")
      (node (ref "C13") (pin "+") (pinfunction "+_+") (pintype "passive"))
      (node (ref "C32") (pin "1") (pinfunction "1_1") (pintype "passive"))
      (node (ref "C38") (pin "1") (pinfunction "1_1") (pintype "passive"))
      (node (ref "C39") (pin "1") (pinfunction "1_1") (pintype "passive"))
      (node (ref "C40") (pin "1") (pinfunction "1_1") (pintype "passive"))
      (node (ref "C41") (pin "1") (pinfunction "1_1") (pintype "passive"))
      (node (ref "C42") (pin "1") (pinfunction "1_1") (pintype "passive"))
      (node (ref "C43") (pin "1") (pinfunction "1_1") (pintype "passive"))
      (node (ref "C44") (pin "1") (pinfunction "1_1") (pintype "passive"))
      (node (ref "J49") (pin "1") (pinfunction "1_1") (pintype "passive"))
      (node (ref "J50") (pin "1") (pinfunction "1_1") (pintype "passive"))
      (node (ref "J51") (pin "1") (pinfunction "1_1") (pintype "passive"))
      (node (ref "J52") (pin "1") (pinfunction "1_1") (pintype "passive"))
      (node (ref "J53") (pin "1") (pinfunction "1_1") (pintype "passive"))
      (node (ref "J54") (pin "1") (pinfunction "1_1") (pintype "passive"))
      (node (ref "J55") (pin "1") (pinfunction "1_1") (pintype "passive"))
      (node (ref "J56") (pin "1") (pinfunction "1_1") (pintype "passive"))
      (node (ref "J57") (pin "1") (pinfunction "1_1") (pintype "passive"))
      (node (ref "J58") (pin "1") (pinfunction "1_1") (pintype "passive"))
      (node (ref "J59") (pin "1") (pinfunction "1_1") (pintype "passive"))
      (node (ref "J60") (pin "1") (pinfunction "1_1") (pintype "passive"))
      (node (ref "J61") (pin "1") (pinfunction "1_1") (pintype "passive"))
      (node (ref "J62") (pin "1") (pinfunction "1_1") (pintype "passive"))
      (node (ref "J63") (pin "1") (pinfunction "1_1") (pintype "passive"))
      (node (ref "J64") (pin "1") (pinfunction "1_1") (pintype "passive"))
      (node (ref "JP11") (pin "2") (pinfunction "2_2") (pintype "passive"))
      (node (ref "JP11") (pin "4") (pinfunction "4_4") (pintype "passive"))
      (node (ref "JP12") (pin "2") (pinfunction "2_2") (pintype "passive"))
      (node (ref "JP12") (pin "4") (pinfunction "4_4") (pintype "passive"))
      (node (ref "JP6") (pin "1") (pinfunction "1_1") (pintype "passive"))
      (node (ref "JP6") (pin "2") (pinfunction "2_2") (pintype "passive"))
      (node (ref "JP6") (pin "3") (pinfunction "3_3") (pintype "passive"))
      (node (ref "JP6") (pin "4") (pinfunction "4_4") (pintype "passive"))
      (node (ref "JP7") (pin "1") (pinfunction "1_1") (pintype "passive"))
      (node (ref "JP7") (pin "2") (pinfunction "2_2") (pintype "passive"))
      (node (ref "JP7") (pin "3") (pinfunction "3_3") (pintype "passive"))
      (node (ref "JP7") (pin "4") (pinfunction "4_4") (pintype "passive"))
      (node (ref "JP9") (pin "2") (pinfunction "2_2") (pintype "passive"))
      (node (ref "PL1") (pin "23") (pinfunction "S_23") (pintype "passive"))
      (node (ref "R5") (pin "2") (pinfunction "2_2") (pintype "passive"))
      (node (ref "U18") (pin "14") (pinfunction "REF_IN(+)_14") (pintype "passive"))
      (node (ref "U18") (pin "9") (pinfunction "AVDD_9") (pintype "passive"))
      (node (ref "U21") (pin "14") (pinfunction "REF_IN(+)_14") (pintype "passive"))
      (node (ref "U21") (pin "9") (pinfunction "AVDD_9") (pintype "passive"))
      (node (ref "U23") (pin "14") (pinfunction "REF_IN(+)_14") (pintype "passive"))
      (node (ref "U23") (pin "9") (pinfunction "AVDD_9") (pintype "passive"))
      (node (ref "U24") (pin "14") (pinfunction "REF_IN(+)_14") (pintype "passive"))
      (node (ref "U24") (pin "9") (pinfunction "AVDD_9") (pintype "passive"))
      (node (ref "U25") (pin "14") (pinfunction "REF_IN(+)_14") (pintype "passive"))
      (node (ref "U25") (pin "9") (pinfunction "AVDD_9") (pintype "passive"))
      (node (ref "U26") (pin "14") (pinfunction "REF_IN(+)_14") (pintype "passive"))
      (node (ref "U26") (pin "9") (pinfunction "AVDD_9") (pintype "passive"))
      (node (ref "U27") (pin "14") (pinfunction "REF_IN(+)_14") (pintype "passive"))
      (node (ref "U27") (pin "9") (pinfunction "AVDD_9") (pintype "passive"))
      (node (ref "U28") (pin "14") (pinfunction "REF_IN(+)_14") (pintype "passive"))
      (node (ref "U28") (pin "9") (pinfunction "AVDD_9") (pintype "passive"))
      (node (ref "U5") (pin "15") (pinfunction "AVDD_3_15") (pintype "passive"))
      (node (ref "U5") (pin "30") (pinfunction "AVDD_4_30") (pintype "passive"))
      (node (ref "U5") (pin "6") (pinfunction "AVDD_2_6") (pintype "passive"))
      (node (ref "U5") (pin "71") (pinfunction "AVDD_71") (pintype "passive"))
    )
    (net (code "2") (name "+5V_CURR_LIM") (class "Default")
      (node (ref "LED2") (pin "A") (pinfunction "A_A") (pintype "passive"))
      (node (ref "R5") (pin "1") (pinfunction "1_1") (pintype "passive"))
    )
    (net (code "3") (name "3_3V") (class "Default")
      (node (ref "SV1") (pin "17") (pinfunction "17_17") (pintype "passive"))
    )
    (net (code "4") (name "ADC2_0") (class "Default")
      (node (ref "J32") (pin "3") (pinfunction "3_3") (pintype "input"))
      (node (ref "JP4") (pin "1") (pinfunction "1_1") (pintype "passive"))
      (node (ref "U5") (pin "28") (pinfunction "V0A_28") (pintype "passive"))
    )
    (net (code "5") (name "ADC2_1") (class "Default")
      (node (ref "J31") (pin "3") (pinfunction "3_3") (pintype "input"))
      (node (ref "JP4") (pin "3") (pinfunction "3_3") (pintype "passive"))
      (node (ref "U5") (pin "26") (pinfunction "V1A_26") (pintype "passive"))
    )
    (net (code "6") (name "ADC2_2") (class "Default")
      (node (ref "J30") (pin "3") (pinfunction "3_3") (pintype "input"))
      (node (ref "JP4") (pin "5") (pinfunction "5_5") (pintype "passive"))
      (node (ref "U5") (pin "24") (pinfunction "V2A_24") (pintype "passive"))
    )
    (net (code "7") (name "ADC2_3") (class "Default")
      (node (ref "J29") (pin "3") (pinfunction "3_3") (pintype "input"))
      (node (ref "JP4") (pin "7") (pinfunction "7_7") (pintype "passive"))
      (node (ref "U5") (pin "22") (pinfunction "V3A_22") (pintype "passive"))
    )
    (net (code "8") (name "ADC2_4") (class "Default")
      (node (ref "J28") (pin "3") (pinfunction "3_3") (pintype "input"))
      (node (ref "JP4") (pin "9") (pinfunction "9_9") (pintype "passive"))
      (node (ref "U5") (pin "19") (pinfunction "V4A_19") (pintype "passive"))
    )
    (net (code "9") (name "ADC2_5") (class "Default")
      (node (ref "J27") (pin "3") (pinfunction "3_3") (pintype "input"))
      (node (ref "JP4") (pin "11") (pinfunction "11_11") (pintype "passive"))
      (node (ref "U5") (pin "17") (pinfunction "V5A_17") (pintype "passive"))
    )
    (net (code "10") (name "ADC2_6") (class "Default")
      (node (ref "J26") (pin "3") (pinfunction "3_3") (pintype "input"))
      (node (ref "JP4") (pin "13") (pinfunction "13_13") (pintype "passive"))
      (node (ref "U5") (pin "14") (pinfunction "V6A_14") (pintype "passive"))
    )
    (net (code "11") (name "ADC2_7") (class "Default")
      (node (ref "J25") (pin "3") (pinfunction "3_3") (pintype "input"))
      (node (ref "JP4") (pin "15") (pinfunction "15_15") (pintype "passive"))
      (node (ref "U5") (pin "12") (pinfunction "V7A_12") (pintype "passive"))
    )
    (net (code "12") (name "ADC2_8") (class "Default")
      (node (ref "J17") (pin "3") (pinfunction "3_3") (pintype "input"))
      (node (ref "JP3") (pin "15") (pinfunction "15_15") (pintype "passive"))
      (node (ref "U5") (pin "73") (pinfunction "V0B_73") (pintype "passive"))
    )
    (net (code "13") (name "ADC2_9") (class "Default")
      (node (ref "J18") (pin "3") (pinfunction "3_3") (pintype "input"))
      (node (ref "JP3") (pin "13") (pinfunction "13_13") (pintype "passive"))
      (node (ref "U5") (pin "75") (pinfunction "V1B_75") (pintype "passive"))
    )
    (net (code "14") (name "ADC2_10") (class "Default")
      (node (ref "J19") (pin "3") (pinfunction "3_3") (pintype "input"))
      (node (ref "JP3") (pin "11") (pinfunction "11_11") (pintype "passive"))
      (node (ref "U5") (pin "77") (pinfunction "V2B_77") (pintype "passive"))
    )
    (net (code "15") (name "ADC2_11") (class "Default")
      (node (ref "J20") (pin "3") (pinfunction "3_3") (pintype "input"))
      (node (ref "JP3") (pin "9") (pinfunction "9_9") (pintype "passive"))
      (node (ref "U5") (pin "79") (pinfunction "V3B_79") (pintype "passive"))
    )
    (net (code "16") (name "ADC2_12") (class "Default")
      (node (ref "J21") (pin "3") (pinfunction "3_3") (pintype "input"))
      (node (ref "JP3") (pin "7") (pinfunction "7_7") (pintype "passive"))
      (node (ref "U5") (pin "2") (pinfunction "V4B_2") (pintype "passive"))
    )
    (net (code "17") (name "ADC2_13") (class "Default")
      (node (ref "J22") (pin "3") (pinfunction "3_3") (pintype "input"))
      (node (ref "JP3") (pin "5") (pinfunction "5_5") (pintype "passive"))
      (node (ref "U5") (pin "4") (pinfunction "V5B_4") (pintype "passive"))
    )
    (net (code "18") (name "ADC2_14") (class "Default")
      (node (ref "J23") (pin "3") (pinfunction "3_3") (pintype "input"))
      (node (ref "JP3") (pin "3") (pinfunction "3_3") (pintype "passive"))
      (node (ref "U5") (pin "7") (pinfunction "V6B_7") (pintype "passive"))
    )
    (net (code "19") (name "ADC2_15") (class "Default")
      (node (ref "J24") (pin "3") (pinfunction "3_3") (pintype "input"))
      (node (ref "JP3") (pin "1") (pinfunction "1_1") (pintype "passive"))
      (node (ref "U5") (pin "9") (pinfunction "V7B_9") (pintype "passive"))
    )
    (net (code "20") (name "ADC_2_COM_MODE") (class "Default")
      (node (ref "R2") (pin "1") (pinfunction "1_1") (pintype "passive"))
      (node (ref "U5") (pin "40") (pinfunction "*PAR/SER_40") (pintype "passive"))
    )
    (net (code "21") (name "ADC_2_CONVST") (class "Default")
      (node (ref "SV1") (pin "5") (pinfunction "5_5") (pintype "passive"))
      (node (ref "U$1") (pin "2-OUT2") (pinfunction "2-OUT2_2-OUT2") (pintype "bidirectional"))
      (node (ref "U5") (pin "68") (pinfunction "CONVST_68") (pintype "passive"))
    )
    (net (code "22") (name "ADC_2_REFCAP") (class "Default")
      (node (ref "C45") (pin "2") (pinfunction "2_2") (pintype "passive"))
      (node (ref "U5") (pin "31") (pinfunction "REFCAP_31") (pintype "passive"))
    )
    (net (code "23") (name "ADC_2_REFINOUT") (class "Default")
      (node (ref "C62") (pin "2") (pinfunction "2_2") (pintype "passive"))
      (node (ref "R6") (pin "1") (pinfunction "1_1") (pintype "passive"))
      (node (ref "U5") (pin "33") (pinfunction "REFINOUT_33") (pintype "passive"))
    )
    (net (code "24") (name "ADC_2_REGCAP") (class "Default")
      (node (ref "C48") (pin "1") (pinfunction "1_1") (pintype "passive"))
      (node (ref "C49") (pin "1") (pinfunction "1_1") (pintype "passive"))
      (node (ref "U5") (pin "70") (pinfunction "REGCAP_70") (pintype "passive"))
    )
    (net (code "25") (name "ADC_2_REGCAPD") (class "Default")
      (node (ref "C50") (pin "1") (pinfunction "1_1") (pintype "passive"))
      (node (ref "C51") (pin "1") (pinfunction "1_1") (pintype "passive"))
      (node (ref "U5") (pin "52") (pinfunction "REGCAPD_52") (pintype "passive"))
    )
    (net (code "26") (name "ADC_2_RST") (class "Default")
      (node (ref "R4") (pin "1") (pinfunction "1_1") (pintype "passive"))
      (node (ref "S2") (pin "1") (pinfunction "S_1") (pintype "passive"))
      (node (ref "U5") (pin "36") (pinfunction "*RESET_36") (pintype "passive"))
    )
    (net (code "27") (name "ADC_2_VREF") (class "Default")
      (node (ref "C28") (pin "+") (pinfunction "+_+") (pintype "passive"))
      (node (ref "C35") (pin "1") (pinfunction "1_1") (pintype "passive"))
      (node (ref "C36") (pin "1") (pinfunction "1_1") (pintype "passive"))
      (node (ref "R6") (pin "2") (pinfunction "2_2") (pintype "passive"))
      (node (ref "U4") (pin "6") (pinfunction "VOUT_6") (pintype "passive"))
    )
    (net (code "28") (name "BT_1_AIN1_+") (class "Default")
      (node (ref "J49") (pin "3") (pinfunction "3_3") (pintype "passive"))
      (node (ref "JP10") (pin "2") (pinfunction "2_2") (pintype "passive"))
      (node (ref "U18") (pin "10") (pinfunction "AIN1(+)_10") (pintype "passive"))
    )
    (net (code "29") (name "BT_1_AIN1_-") (class "Default")
      (node (ref "J49") (pin "4") (pinfunction "4_4") (pintype "passive"))
      (node (ref "JP10") (pin "1") (pinfunction "1_1") (pintype "passive"))
      (node (ref "U18") (pin "11") (pinfunction "AIN1(-)_11") (pintype "passive"))
    )
    (net (code "30") (name "BT_1_AIN2_+") (class "Default")
      (node (ref "J50") (pin "3") (pinfunction "3_3") (pintype "passive"))
      (node (ref "JP10") (pin "4") (pinfunction "4_4") (pintype "passive"))
      (node (ref "U18") (pin "12") (pinfunction "AIN2(+)D1_12") (pintype "passive"))
    )
    (net (code "31") (name "BT_1_AIN2_-") (class "Default")
      (node (ref "J50") (pin "4") (pinfunction "4_4") (pintype "passive"))
      (node (ref "JP10") (pin "3") (pinfunction "3_3") (pintype "passive"))
      (node (ref "U18") (pin "13") (pinfunction "AIN2(-)D0_13") (pintype "passive"))
    )
    (net (code "32") (name "BT_1_MCLK_OUT") (class "Default")
      (node (ref "U18") (pin "3") (pinfunction "MCLK_OUT_3") (pintype "passive"))
      (node (ref "U21") (pin "2") (pinfunction "MCLK_IN_2") (pintype "passive"))
    )
    (net (code "33") (name "BT_2_AIN1_+") (class "Default")
      (node (ref "J51") (pin "3") (pinfunction "3_3") (pintype "passive"))
      (node (ref "JP10") (pin "6") (pinfunction "6_6") (pintype "passive"))
      (node (ref "U21") (pin "10") (pinfunction "AIN1(+)_10") (pintype "passive"))
    )
    (net (code "34") (name "BT_2_AIN1_-") (class "Default")
      (node (ref "J51") (pin "4") (pinfunction "4_4") (pintype "passive"))
      (node (ref "JP10") (pin "5") (pinfunction "5_5") (pintype "passive"))
      (node (ref "U21") (pin "11") (pinfunction "AIN1(-)_11") (pintype "passive"))
    )
    (net (code "35") (name "BT_2_AIN2_+") (class "Default")
      (node (ref "J52") (pin "3") (pinfunction "3_3") (pintype "passive"))
      (node (ref "JP10") (pin "8") (pinfunction "8_8") (pintype "passive"))
      (node (ref "U21") (pin "12") (pinfunction "AIN2(+)D1_12") (pintype "passive"))
    )
    (net (code "36") (name "BT_2_AIN2_-") (class "Default")
      (node (ref "J52") (pin "4") (pinfunction "4_4") (pintype "passive"))
      (node (ref "JP10") (pin "7") (pinfunction "7_7") (pintype "passive"))
      (node (ref "U21") (pin "13") (pinfunction "AIN2(-)D0_13") (pintype "passive"))
    )
    (net (code "37") (name "BT_2_MCLK_OUT") (class "Default")
      (node (ref "U21") (pin "3") (pinfunction "MCLK_OUT_3") (pintype "passive"))
      (node (ref "U23") (pin "2") (pinfunction "MCLK_IN_2") (pintype "passive"))
    )
    (net (code "38") (name "BT_3_AIN1_+") (class "Default")
      (node (ref "J53") (pin "3") (pinfunction "3_3") (pintype "passive"))
      (node (ref "JP10") (pin "10") (pinfunction "10_10") (pintype "passive"))
      (node (ref "U23") (pin "10") (pinfunction "AIN1(+)_10") (pintype "passive"))
    )
    (net (code "39") (name "BT_3_AIN1_-") (class "Default")
      (node (ref "J53") (pin "4") (pinfunction "4_4") (pintype "passive"))
      (node (ref "JP10") (pin "9") (pinfunction "9_9") (pintype "passive"))
      (node (ref "U23") (pin "11") (pinfunction "AIN1(-)_11") (pintype "passive"))
    )
    (net (code "40") (name "BT_3_AIN2_+") (class "Default")
      (node (ref "J54") (pin "3") (pinfunction "3_3") (pintype "passive"))
      (node (ref "JP10") (pin "12") (pinfunction "12_12") (pintype "passive"))
      (node (ref "U23") (pin "12") (pinfunction "AIN2(+)D1_12") (pintype "passive"))
    )
    (net (code "41") (name "BT_3_AIN2_-") (class "Default")
      (node (ref "J54") (pin "4") (pinfunction "4_4") (pintype "passive"))
      (node (ref "JP10") (pin "11") (pinfunction "11_11") (pintype "passive"))
      (node (ref "U23") (pin "13") (pinfunction "AIN2(-)D0_13") (pintype "passive"))
    )
    (net (code "42") (name "BT_3_MCLK_OUT") (class "Default")
      (node (ref "U23") (pin "3") (pinfunction "MCLK_OUT_3") (pintype "passive"))
      (node (ref "U24") (pin "2") (pinfunction "MCLK_IN_2") (pintype "passive"))
    )
    (net (code "43") (name "BT_4_AIN1_+") (class "Default")
      (node (ref "J55") (pin "3") (pinfunction "3_3") (pintype "passive"))
      (node (ref "JP10") (pin "14") (pinfunction "14_14") (pintype "passive"))
      (node (ref "U24") (pin "10") (pinfunction "AIN1(+)_10") (pintype "passive"))
    )
    (net (code "44") (name "BT_4_AIN1_-") (class "Default")
      (node (ref "J55") (pin "4") (pinfunction "4_4") (pintype "passive"))
      (node (ref "JP10") (pin "13") (pinfunction "13_13") (pintype "passive"))
      (node (ref "U24") (pin "11") (pinfunction "AIN1(-)_11") (pintype "passive"))
    )
    (net (code "45") (name "BT_4_AIN2_+") (class "Default")
      (node (ref "J56") (pin "3") (pinfunction "3_3") (pintype "passive"))
      (node (ref "JP10") (pin "16") (pinfunction "16_16") (pintype "passive"))
      (node (ref "U24") (pin "12") (pinfunction "AIN2(+)D1_12") (pintype "passive"))
    )
    (net (code "46") (name "BT_4_AIN2_-") (class "Default")
      (node (ref "J56") (pin "4") (pinfunction "4_4") (pintype "passive"))
      (node (ref "JP10") (pin "15") (pinfunction "15_15") (pintype "passive"))
      (node (ref "U24") (pin "13") (pinfunction "AIN2(-)D0_13") (pintype "passive"))
    )
    (net (code "47") (name "BT_4_MCLK_OUT") (class "Default")
      (node (ref "U25") (pin "2") (pinfunction "MCLK_IN_2") (pintype "passive"))
      (node (ref "Y1") (pin "3") (pinfunction "OUT_3") (pintype "bidirectional"))
    )
    (net (code "48") (name "BT_5_AIN1_+") (class "Default")
      (node (ref "J57") (pin "3") (pinfunction "3_3") (pintype "passive"))
      (node (ref "JP5") (pin "2") (pinfunction "2_2") (pintype "passive"))
      (node (ref "U25") (pin "10") (pinfunction "AIN1(+)_10") (pintype "passive"))
    )
    (net (code "49") (name "BT_5_AIN1_-") (class "Default")
      (node (ref "J57") (pin "4") (pinfunction "4_4") (pintype "passive"))
      (node (ref "JP5") (pin "1") (pinfunction "1_1") (pintype "passive"))
      (node (ref "U25") (pin "11") (pinfunction "AIN1(-)_11") (pintype "passive"))
    )
    (net (code "50") (name "BT_5_AIN2_+") (class "Default")
      (node (ref "J58") (pin "3") (pinfunction "3_3") (pintype "passive"))
      (node (ref "JP5") (pin "4") (pinfunction "4_4") (pintype "passive"))
      (node (ref "U25") (pin "12") (pinfunction "AIN2(+)D1_12") (pintype "passive"))
    )
    (net (code "51") (name "BT_5_AIN2_-") (class "Default")
      (node (ref "J58") (pin "4") (pinfunction "4_4") (pintype "passive"))
      (node (ref "JP5") (pin "3") (pinfunction "3_3") (pintype "passive"))
      (node (ref "U25") (pin "13") (pinfunction "AIN2(-)D0_13") (pintype "passive"))
    )
    (net (code "52") (name "BT_5_MCLK_OUT") (class "Default")
      (node (ref "U25") (pin "3") (pinfunction "MCLK_OUT_3") (pintype "passive"))
      (node (ref "U26") (pin "2") (pinfunction "MCLK_IN_2") (pintype "passive"))
    )
    (net (code "53") (name "BT_6_AIN1_+") (class "Default")
      (node (ref "J59") (pin "3") (pinfunction "3_3") (pintype "passive"))
      (node (ref "JP5") (pin "6") (pinfunction "6_6") (pintype "passive"))
      (node (ref "U26") (pin "10") (pinfunction "AIN1(+)_10") (pintype "passive"))
    )
    (net (code "54") (name "BT_6_AIN1_-") (class "Default")
      (node (ref "J59") (pin "4") (pinfunction "4_4") (pintype "passive"))
      (node (ref "JP5") (pin "5") (pinfunction "5_5") (pintype "passive"))
      (node (ref "U26") (pin "11") (pinfunction "AIN1(-)_11") (pintype "passive"))
    )
    (net (code "55") (name "BT_6_AIN2_+") (class "Default")
      (node (ref "J60") (pin "3") (pinfunction "3_3") (pintype "passive"))
      (node (ref "JP5") (pin "8") (pinfunction "8_8") (pintype "passive"))
      (node (ref "U26") (pin "12") (pinfunction "AIN2(+)D1_12") (pintype "passive"))
    )
    (net (code "56") (name "BT_6_AIN2_-") (class "Default")
      (node (ref "J60") (pin "4") (pinfunction "4_4") (pintype "passive"))
      (node (ref "JP5") (pin "7") (pinfunction "7_7") (pintype "passive"))
      (node (ref "U26") (pin "13") (pinfunction "AIN2(-)D0_13") (pintype "passive"))
    )
    (net (code "57") (name "BT_6_MCLK_OUT") (class "Default")
      (node (ref "U26") (pin "3") (pinfunction "MCLK_OUT_3") (pintype "passive"))
      (node (ref "U27") (pin "2") (pinfunction "MCLK_IN_2") (pintype "passive"))
    )
    (net (code "58") (name "BT_7_AIN1_+") (class "Default")
      (node (ref "J61") (pin "3") (pinfunction "3_3") (pintype "passive"))
      (node (ref "JP5") (pin "10") (pinfunction "10_10") (pintype "passive"))
      (node (ref "U27") (pin "10") (pinfunction "AIN1(+)_10") (pintype "passive"))
    )
    (net (code "59") (name "BT_7_AIN1_-") (class "Default")
      (node (ref "J61") (pin "4") (pinfunction "4_4") (pintype "passive"))
      (node (ref "JP5") (pin "9") (pinfunction "9_9") (pintype "passive"))
      (node (ref "U27") (pin "11") (pinfunction "AIN1(-)_11") (pintype "passive"))
    )
    (net (code "60") (name "BT_7_AIN2_+") (class "Default")
      (node (ref "J62") (pin "3") (pinfunction "3_3") (pintype "passive"))
      (node (ref "JP5") (pin "12") (pinfunction "12_12") (pintype "passive"))
      (node (ref "U27") (pin "12") (pinfunction "AIN2(+)D1_12") (pintype "passive"))
    )
    (net (code "61") (name "BT_7_AIN2_-") (class "Default")
      (node (ref "J62") (pin "4") (pinfunction "4_4") (pintype "passive"))
      (node (ref "JP5") (pin "11") (pinfunction "11_11") (pintype "passive"))
      (node (ref "U27") (pin "13") (pinfunction "AIN2(-)D0_13") (pintype "passive"))
    )
    (net (code "62") (name "BT_7_MCLK_OUT") (class "Default")
      (node (ref "U27") (pin "3") (pinfunction "MCLK_OUT_3") (pintype "passive"))
      (node (ref "U28") (pin "2") (pinfunction "MCLK_IN_2") (pintype "passive"))
    )
    (net (code "63") (name "BT_8_AIN1_+") (class "Default")
      (node (ref "J63") (pin "3") (pinfunction "3_3") (pintype "passive"))
      (node (ref "JP5") (pin "14") (pinfunction "14_14") (pintype "passive"))
      (node (ref "U28") (pin "10") (pinfunction "AIN1(+)_10") (pintype "passive"))
    )
    (net (code "64") (name "BT_8_AIN1_-") (class "Default")
      (node (ref "J63") (pin "4") (pinfunction "4_4") (pintype "passive"))
      (node (ref "JP5") (pin "13") (pinfunction "13_13") (pintype "passive"))
      (node (ref "U28") (pin "11") (pinfunction "AIN1(-)_11") (pintype "passive"))
    )
    (net (code "65") (name "BT_8_AIN2_+") (class "Default")
      (node (ref "J64") (pin "3") (pinfunction "3_3") (pintype "passive"))
      (node (ref "JP5") (pin "16") (pinfunction "16_16") (pintype "passive"))
      (node (ref "U28") (pin "12") (pinfunction "AIN2(+)D1_12") (pintype "passive"))
    )
    (net (code "66") (name "BT_8_AIN2_-") (class "Default")
      (node (ref "J64") (pin "4") (pinfunction "4_4") (pintype "passive"))
      (node (ref "JP5") (pin "15") (pinfunction "15_15") (pintype "passive"))
      (node (ref "U28") (pin "13") (pinfunction "AIN2(-)D0_13") (pintype "passive"))
    )
    (net (code "67") (name "DAC2_0") (class "Default")
      (node (ref "JP2") (pin "15") (pinfunction "15_15") (pintype "passive"))
      (node (ref "U19") (pin "34") (pinfunction "VOUT0_34") (pintype "passive"))
      (node (ref "U2") (pin "15") (pinfunction "15_15") (pintype "passive"))
    )
    (net (code "68") (name "DAC2_1") (class "Default")
      (node (ref "JP2") (pin "13") (pinfunction "13_13") (pintype "passive"))
      (node (ref "U19") (pin "35") (pinfunction "VOUT1_35") (pintype "passive"))
      (node (ref "U2") (pin "13") (pinfunction "13_13") (pintype "passive"))
    )
    (net (code "69") (name "DAC2_2") (class "Default")
      (node (ref "JP2") (pin "11") (pinfunction "11_11") (pintype "passive"))
      (node (ref "U19") (pin "36") (pinfunction "VOUT2_36") (pintype "passive"))
      (node (ref "U2") (pin "11") (pinfunction "11_11") (pintype "passive"))
    )
    (net (code "70") (name "DAC2_3") (class "Default")
      (node (ref "JP2") (pin "9") (pinfunction "9_9") (pintype "passive"))
      (node (ref "U19") (pin "37") (pinfunction "VOUT3_37") (pintype "passive"))
      (node (ref "U2") (pin "9") (pinfunction "9_9") (pintype "passive"))
    )
    (net (code "71") (name "DAC2_4") (class "Default")
      (node (ref "JP2") (pin "7") (pinfunction "7_7") (pintype "passive"))
      (node (ref "U19") (pin "39") (pinfunction "VOUT4_39") (pintype "passive"))
      (node (ref "U2") (pin "7") (pinfunction "7_7") (pintype "passive"))
    )
    (net (code "72") (name "DAC2_5") (class "Default")
      (node (ref "JP2") (pin "5") (pinfunction "5_5") (pintype "passive"))
      (node (ref "U19") (pin "40") (pinfunction "VOUT5_40") (pintype "passive"))
      (node (ref "U2") (pin "5") (pinfunction "5_5") (pintype "passive"))
    )
    (net (code "73") (name "DAC2_6") (class "Default")
      (node (ref "JP2") (pin "3") (pinfunction "3_3") (pintype "passive"))
      (node (ref "U19") (pin "41") (pinfunction "VOUT6_41") (pintype "passive"))
      (node (ref "U2") (pin "3") (pinfunction "3_3") (pintype "passive"))
    )
    (net (code "74") (name "DAC2_7") (class "Default")
      (node (ref "JP2") (pin "1") (pinfunction "1_1") (pintype "passive"))
      (node (ref "U19") (pin "42") (pinfunction "VOUT7_42") (pintype "passive"))
      (node (ref "U2") (pin "1") (pinfunction "1_1") (pintype "passive"))
    )
    (net (code "75") (name "DAC2_8") (class "Default")
      (node (ref "JP2") (pin "31") (pinfunction "31_31") (pintype "passive"))
      (node (ref "U19") (pin "15") (pinfunction "VOUT8_15") (pintype "passive"))
      (node (ref "U2") (pin "31") (pinfunction "31_31") (pintype "passive"))
    )
    (net (code "76") (name "DAC2_9") (class "Default")
      (node (ref "JP2") (pin "29") (pinfunction "29_29") (pintype "passive"))
      (node (ref "U19") (pin "16") (pinfunction "VOUT9_16") (pintype "passive"))
      (node (ref "U2") (pin "29") (pinfunction "29_29") (pintype "passive"))
    )
    (net (code "77") (name "DAC2_10") (class "Default")
      (node (ref "JP2") (pin "27") (pinfunction "27_27") (pintype "passive"))
      (node (ref "U19") (pin "17") (pinfunction "VOUT10_17") (pintype "passive"))
      (node (ref "U2") (pin "27") (pinfunction "27_27") (pintype "passive"))
    )
    (net (code "78") (name "DAC2_11") (class "Default")
      (node (ref "JP2") (pin "25") (pinfunction "25_25") (pintype "passive"))
      (node (ref "U19") (pin "18") (pinfunction "VOUT11_18") (pintype "passive"))
      (node (ref "U2") (pin "25") (pinfunction "25_25") (pintype "passive"))
    )
    (net (code "79") (name "DAC2_12") (class "Default")
      (node (ref "JP2") (pin "23") (pinfunction "23_23") (pintype "passive"))
      (node (ref "U19") (pin "20") (pinfunction "VOUT12_20") (pintype "passive"))
      (node (ref "U2") (pin "23") (pinfunction "23_23") (pintype "passive"))
    )
    (net (code "80") (name "DAC2_13") (class "Default")
      (node (ref "JP2") (pin "21") (pinfunction "21_21") (pintype "passive"))
      (node (ref "U19") (pin "21") (pinfunction "VOUT13_21") (pintype "passive"))
      (node (ref "U2") (pin "21") (pinfunction "21_21") (pintype "passive"))
    )
    (net (code "81") (name "DAC2_14") (class "Default")
      (node (ref "JP2") (pin "19") (pinfunction "19_19") (pintype "passive"))
      (node (ref "U19") (pin "22") (pinfunction "VOUT14_22") (pintype "passive"))
      (node (ref "U2") (pin "19") (pinfunction "19_19") (pintype "passive"))
    )
    (net (code "82") (name "DAC2_15") (class "Default")
      (node (ref "JP2") (pin "17") (pinfunction "17_17") (pintype "passive"))
      (node (ref "U19") (pin "23") (pinfunction "VOUT15_23") (pintype "passive"))
      (node (ref "U2") (pin "17") (pinfunction "17_17") (pintype "passive"))
    )
    (net (code "83") (name "DAC_2_CLR") (class "Default")
      (node (ref "R20") (pin "2") (pinfunction "2_2") (pintype "passive"))
      (node (ref "U19") (pin "2") (pinfunction "*CLR_2") (pintype "passive"))
    )
    (net (code "84") (name "DAC_2_RST") (class "Default")
      (node (ref "R19") (pin "2") (pinfunction "2_2") (pintype "passive"))
      (node (ref "S8") (pin "4") (pinfunction "P1_4") (pintype "passive"))
      (node (ref "U19") (pin "3") (pinfunction "*RESET_3") (pintype "passive"))
    )
    (net (code "85") (name "DVCC") (class "Default")
      (node (ref "C1") (pin "2") (pinfunction "2_2") (pintype "passive"))
      (node (ref "C11") (pin "2") (pinfunction "2_2") (pintype "passive"))
      (node (ref "C136") (pin "1") (pinfunction "1_1") (pintype "passive"))
      (node (ref "C137") (pin "1") (pinfunction "1_1") (pintype "passive"))
      (node (ref "C14") (pin "+") (pinfunction "+_+") (pintype "passive"))
      (node (ref "C19") (pin "1") (pinfunction "1_1") (pintype "passive"))
      (node (ref "C2") (pin "1") (pinfunction "1_1") (pintype "passive"))
      (node (ref "C20") (pin "1") (pinfunction "1_1") (pintype "passive"))
      (node (ref "C21") (pin "+") (pinfunction "+_+") (pintype "passive"))
      (node (ref "C22") (pin "+") (pinfunction "+_+") (pintype "passive"))
      (node (ref "C3") (pin "1") (pinfunction "1_1") (pintype "passive"))
      (node (ref "C4") (pin "1") (pinfunction "1_1") (pintype "passive"))
      (node (ref "C46") (pin "1") (pinfunction "1_1") (pintype "passive"))
      (node (ref "C47") (pin "1") (pinfunction "1_1") (pintype "passive"))
      (node (ref "C5") (pin "1") (pinfunction "1_1") (pintype "passive"))
      (node (ref "C6") (pin "1") (pinfunction "1_1") (pintype "passive"))
      (node (ref "C7") (pin "1") (pinfunction "1_1") (pintype "passive"))
      (node (ref "PL1") (pin "2") (pinfunction "S_2") (pintype "passive"))
      (node (ref "Q1") (pin "C") (pinfunction "C_C") (pintype "passive"))
      (node (ref "R19") (pin "1") (pinfunction "1_1") (pintype "passive"))
      (node (ref "R2") (pin "2") (pinfunction "2_2") (pintype "passive"))
      (node (ref "R20") (pin "1") (pinfunction "1_1") (pintype "passive"))
      (node (ref "R3") (pin "2") (pinfunction "2_2") (pintype "passive"))
      (node (ref "R4") (pin "2") (pinfunction "2_2") (pintype "passive"))
      (node (ref "U18") (pin "18") (pinfunction "*STANDBY_18") (pintype "passive"))
      (node (ref "U18") (pin "23") (pinfunction "DVDD_23") (pintype "passive"))
      (node (ref "U18") (pin "5") (pinfunction "*SYNC_5") (pintype "passive"))
      (node (ref "U18") (pin "6") (pinfunction "*RESET_6") (pintype "passive"))
      (node (ref "U19") (pin "44") (pinfunction "DVCC_2_44") (pintype "passive"))
      (node (ref "U19") (pin "50") (pinfunction "DVCC_50") (pintype "passive"))
      (node (ref "U21") (pin "18") (pinfunction "*STANDBY_18") (pintype "passive"))
      (node (ref "U21") (pin "23") (pinfunction "DVDD_23") (pintype "passive"))
      (node (ref "U21") (pin "5") (pinfunction "*SYNC_5") (pintype "passive"))
      (node (ref "U21") (pin "6") (pinfunction "*RESET_6") (pintype "passive"))
      (node (ref "U23") (pin "18") (pinfunction "*STANDBY_18") (pintype "passive"))
      (node (ref "U23") (pin "23") (pinfunction "DVDD_23") (pintype "passive"))
      (node (ref "U23") (pin "5") (pinfunction "*SYNC_5") (pintype "passive"))
      (node (ref "U23") (pin "6") (pinfunction "*RESET_6") (pintype "passive"))
      (node (ref "U24") (pin "18") (pinfunction "*STANDBY_18") (pintype "passive"))
      (node (ref "U24") (pin "23") (pinfunction "DVDD_23") (pintype "passive"))
      (node (ref "U24") (pin "5") (pinfunction "*SYNC_5") (pintype "passive"))
      (node (ref "U24") (pin "6") (pinfunction "*RESET_6") (pintype "passive"))
      (node (ref "U25") (pin "18") (pinfunction "*STANDBY_18") (pintype "passive"))
      (node (ref "U25") (pin "23") (pinfunction "DVDD_23") (pintype "passive"))
      (node (ref "U25") (pin "5") (pinfunction "*SYNC_5") (pintype "passive"))
      (node (ref "U25") (pin "6") (pinfunction "*RESET_6") (pintype "passive"))
      (node (ref "U26") (pin "18") (pinfunction "*STANDBY_18") (pintype "passive"))
      (node (ref "U26") (pin "23") (pinfunction "DVDD_23") (pintype "passive"))
      (node (ref "U26") (pin "5") (pinfunction "*SYNC_5") (pintype "passive"))
      (node (ref "U26") (pin "6") (pinfunction "*RESET_6") (pintype "passive"))
      (node (ref "U27") (pin "18") (pinfunction "*STANDBY_18") (pintype "passive"))
      (node (ref "U27") (pin "23") (pinfunction "DVDD_23") (pintype "passive"))
      (node (ref "U27") (pin "5") (pinfunction "*SYNC_5") (pintype "passive"))
      (node (ref "U27") (pin "6") (pinfunction "*RESET_6") (pintype "passive"))
      (node (ref "U28") (pin "18") (pinfunction "*STANDBY_18") (pintype "passive"))
      (node (ref "U28") (pin "23") (pinfunction "DVDD_23") (pintype "passive"))
      (node (ref "U28") (pin "5") (pinfunction "*SYNC_5") (pintype "passive"))
      (node (ref "U28") (pin "6") (pinfunction "*RESET_6") (pintype "passive"))
      (node (ref "U5") (pin "49") (pinfunction "VDRIVE_49") (pintype "passive"))
      (node (ref "Y1") (pin "4") (pinfunction "VCC_4") (pintype "bidirectional"))
      (node (ref "Y3") (pin "4") (pinfunction "VCC_4") (pintype "bidirectional"))
    )
    (net (code "86") (name "DVCC_CURR_LIM") (class "Default")
      (node (ref "LED3") (pin "A") (pinfunction "A_A") (pintype "passive"))
      (node (ref "R3") (pin "1") (pinfunction "1_1") (pintype "passive"))
    )
    (net (code "87") (name "D_IO_1") (class "Default")
      (node (ref "JP13") (pin "2") (pinfunction "2_2") (pintype "passive"))
      (node (ref "U$1") (pin "7-RX2/OUT1A") (pinfunction "7-RX2/OUT1A_7-RX2/OUT1A") (pintype "bidirectional"))
    )
    (net (code "88") (name "D_IO_2") (class "Default")
      (node (ref "JP13") (pin "4") (pinfunction "4_4") (pintype "passive"))
      (node (ref "U$1") (pin "8-TX2/IN2") (pinfunction "8-TX2/IN1_8-TX2/IN2") (pintype "bidirectional"))
    )
    (net (code "89") (name "D_IO_3") (class "Default")
      (node (ref "JP13") (pin "6") (pinfunction "6_6") (pintype "passive"))
      (node (ref "U$1") (pin "9-OUT1C") (pinfunction "9-OUT1C_9-OUT1C") (pintype "bidirectional"))
    )
    (net (code "90") (name "D_IO_4") (class "Default")
      (node (ref "JP13") (pin "8") (pinfunction "8_8") (pintype "passive"))
      (node (ref "U$1") (pin "10-CS\\MQSR") (pinfunction "10-CS/MQSR_10-CS\\MQSR") (pintype "bidirectional"))
    )
    (net (code "91") (name "D_IO_5") (class "Default")
      (node (ref "JP13") (pin "10") (pinfunction "10_10") (pintype "passive"))
      (node (ref "U$1") (pin "25-A11/RX6/SDA2") (pinfunction "25-A11/RX6/SDA2_25-A11/RX6/SDA2") (pintype "bidirectional"))
    )
    (net (code "92") (name "D_IO_6") (class "Default")
      (node (ref "JP13") (pin "12") (pinfunction "12_12") (pintype "passive"))
      (node (ref "U$1") (pin "26-A12/MOSI1") (pinfunction "26-A12/MOSI1_26-A12/MOSI1") (pintype "bidirectional"))
    )
    (net (code "93") (name "D_IO_7") (class "Default")
      (node (ref "JP13") (pin "14") (pinfunction "14_14") (pintype "passive"))
      (node (ref "U$1") (pin "27-A13/SCK1") (pinfunction "27-A13/SCK1_27-A13/SCK1") (pintype "bidirectional"))
    )
    (net (code "94") (name "D_IO_8") (class "Default")
      (node (ref "JP13") (pin "16") (pinfunction "16_16") (pintype "passive"))
      (node (ref "U$1") (pin "28-RX7") (pinfunction "28-RX7_28-RX7") (pintype "bidirectional"))
    )
    (net (code "95") (name "D_IO_9") (class "Default")
      (node (ref "JP13") (pin "18") (pinfunction "18_18") (pintype "passive"))
      (node (ref "U$1") (pin "29-TX7") (pinfunction "29-TX7_29-TX7") (pintype "bidirectional"))
    )
    (net (code "96") (name "D_IO_10") (class "Default")
      (node (ref "JP13") (pin "20") (pinfunction "20_20") (pintype "passive"))
      (node (ref "U$1") (pin "30-CRX3") (pinfunction "30-CRX3_30-CRX3") (pintype "bidirectional"))
    )
    (net (code "97") (name "D_IO_11") (class "Default")
      (node (ref "JP13") (pin "22") (pinfunction "22_22") (pintype "passive"))
      (node (ref "U$1") (pin "31-CTX3") (pinfunction "31-CTX3_31-CTX3") (pintype "bidirectional"))
    )
    (net (code "98") (name "D_IO_12") (class "Default")
      (node (ref "JP13") (pin "24") (pinfunction "24_24") (pintype "passive"))
      (node (ref "U$1") (pin "32-OUT1B") (pinfunction "32-OUT1B_32-OUT1B") (pintype "bidirectional"))
    )
    (net (code "99") (name "GND") (class "Default")
      (node (ref "C1") (pin "1") (pinfunction "1_1") (pintype "passive"))
      (node (ref "C10") (pin "-") (pinfunction "-_-") (pintype "passive"))
      (node (ref "C11") (pin "1") (pinfunction "1_1") (pintype "passive"))
      (node (ref "C12") (pin "-") (pinfunction "-_-") (pintype "passive"))
      (node (ref "C13") (pin "-") (pinfunction "-_-") (pintype "passive"))
      (node (ref "C136") (pin "2") (pinfunction "2_2") (pintype "passive"))
      (node (ref "C137") (pin "2") (pinfunction "2_2") (pintype "passive"))
      (node (ref "C14") (pin "-") (pinfunction "-_-") (pintype "passive"))
      (node (ref "C141") (pin "2") (pinfunction "2_2") (pintype "passive"))
      (node (ref "C143") (pin "2") (pinfunction "2_2") (pintype "passive"))
      (node (ref "C145") (pin "2") (pinfunction "2_2") (pintype "passive"))
      (node (ref "C147") (pin "2") (pinfunction "2_2") (pintype "passive"))
      (node (ref "C148") (pin "2") (pinfunction "2_2") (pintype "passive"))
      (node (ref "C15") (pin "-") (pinfunction "-_-") (pintype "passive"))
      (node (ref "C150") (pin "2") (pinfunction "2_2") (pintype "passive"))
      (node (ref "C151") (pin "2") (pinfunction "2_2") (pintype "passive"))
      (node (ref "C16") (pin "+") (pinfunction "+_+") (pintype "passive"))
      (node (ref "C19") (pin "2") (pinfunction "2_2") (pintype "passive"))
      (node (ref "C2") (pin "2") (pinfunction "2_2") (pintype "passive"))
      (node (ref "C20") (pin "2") (pinfunction "2_2") (pintype "passive"))
      (node (ref "C21") (pin "-") (pinfunction "-_-") (pintype "passive"))
      (node (ref "C22") (pin "-") (pinfunction "-_-") (pintype "passive"))
      (node (ref "C23") (pin "-") (pinfunction "-_-") (pintype "passive"))
      (node (ref "C24") (pin "-") (pinfunction "-_-") (pintype "passive"))
      (node (ref "C25") (pin "+") (pinfunction "+_+") (pintype "passive"))
      (node (ref "C26") (pin "+") (pinfunction "+_+") (pintype "passive"))
      (node (ref "C27") (pin "-") (pinfunction "-_-") (pintype "passive"))
      (node (ref "C28") (pin "-") (pinfunction "-_-") (pintype "passive"))
      (node (ref "C3") (pin "2") (pinfunction "2_2") (pintype "passive"))
      (node (ref "C32") (pin "2") (pinfunction "2_2") (pintype "passive"))
      (node (ref "C33") (pin "2") (pinfunction "2_2") (pintype "passive"))
      (node (ref "C35") (pin "2") (pinfunction "2_2") (pintype "passive"))
      (node (ref "C36") (pin "2") (pinfunction "2_2") (pintype "passive"))
      (node (ref "C38") (pin "2") (pinfunction "2_2") (pintype "passive"))
      (node (ref "C39") (pin "2") (pinfunction "2_2") (pintype "passive"))
      (node (ref "C4") (pin "2") (pinfunction "2_2") (pintype "passive"))
      (node (ref "C40") (pin "2") (pinfunction "2_2") (pintype "passive"))
      (node (ref "C41") (pin "2") (pinfunction "2_2") (pintype "passive"))
      (node (ref "C42") (pin "2") (pinfunction "2_2") (pintype "passive"))
      (node (ref "C43") (pin "2") (pinfunction "2_2") (pintype "passive"))
      (node (ref "C44") (pin "2") (pinfunction "2_2") (pintype "passive"))
      (node (ref "C45") (pin "1") (pinfunction "1_1") (pintype "passive"))
      (node (ref "C46") (pin "2") (pinfunction "2_2") (pintype "passive"))
      (node (ref "C47") (pin "2") (pinfunction "2_2") (pintype "passive"))
      (node (ref "C48") (pin "2") (pinfunction "2_2") (pintype "passive"))
      (node (ref "C49") (pin "2") (pinfunction "2_2") (pintype "passive"))
      (node (ref "C5") (pin "2") (pinfunction "2_2") (pintype "passive"))
      (node (ref "C50") (pin "2") (pinfunction "2_2") (pintype "passive"))
      (node (ref "C51") (pin "2") (pinfunction "2_2") (pintype "passive"))
      (node (ref "C6") (pin "2") (pinfunction "2_2") (pintype "passive"))
      (node (ref "C62") (pin "1") (pinfunction "1_1") (pintype "passive"))
      (node (ref "C7") (pin "2") (pinfunction "2_2") (pintype "passive"))
      (node (ref "C8") (pin "-") (pinfunction "-_-") (pintype "passive"))
      (node (ref "C9") (pin "-") (pinfunction "-_-") (pintype "passive"))
      (node (ref "J17") (pin "2") (pinfunction "2_2") (pintype "input"))
      (node (ref "J18") (pin "2") (pinfunction "2_2") (pintype "input"))
      (node (ref "J19") (pin "2") (pinfunction "2_2") (pintype "input"))
      (node (ref "J20") (pin "2") (pinfunction "2_2") (pintype "input"))
      (node (ref "J21") (pin "2") (pinfunction "2_2") (pintype "input"))
      (node (ref "J22") (pin "2") (pinfunction "2_2") (pintype "input"))
      (node (ref "J23") (pin "2") (pinfunction "2_2") (pintype "input"))
      (node (ref "J24") (pin "2") (pinfunction "2_2") (pintype "input"))
      (node (ref "J25") (pin "2") (pinfunction "2_2") (pintype "input"))
      (node (ref "J26") (pin "2") (pinfunction "2_2") (pintype "input"))
      (node (ref "J27") (pin "2") (pinfunction "2_2") (pintype "input"))
      (node (ref "J28") (pin "2") (pinfunction "2_2") (pintype "input"))
      (node (ref "J29") (pin "2") (pinfunction "2_2") (pintype "input"))
      (node (ref "J30") (pin "2") (pinfunction "2_2") (pintype "input"))
      (node (ref "J31") (pin "2") (pinfunction "2_2") (pintype "input"))
      (node (ref "J32") (pin "2") (pinfunction "2_2") (pintype "input"))
      (node (ref "J49") (pin "2") (pinfunction "2_2") (pintype "passive"))
      (node (ref "J50") (pin "2") (pinfunction "2_2") (pintype "passive"))
      (node (ref "J51") (pin "2") (pinfunction "2_2") (pintype "passive"))
      (node (ref "J52") (pin "2") (pinfunction "2_2") (pintype "passive"))
      (node (ref "J53") (pin "2") (pinfunction "2_2") (pintype "passive"))
      (node (ref "J54") (pin "2") (pinfunction "2_2") (pintype "passive"))
      (node (ref "J55") (pin "2") (pinfunction "2_2") (pintype "passive"))
      (node (ref "J56") (pin "2") (pinfunction "2_2") (pintype "passive"))
      (node (ref "J57") (pin "2") (pinfunction "2_2") (pintype "passive"))
      (node (ref "J58") (pin "2") (pinfunction "2_2") (pintype "passive"))
      (node (ref "J59") (pin "2") (pinfunction "2_2") (pintype "passive"))
      (node (ref "J60") (pin "2") (pinfunction "2_2") (pintype "passive"))
      (node (ref "J61") (pin "2") (pinfunction "2_2") (pintype "passive"))
      (node (ref "J62") (pin "2") (pinfunction "2_2") (pintype "passive"))
      (node (ref "J63") (pin "2") (pinfunction "2_2") (pintype "passive"))
      (node (ref "J64") (pin "2") (pinfunction "2_2") (pintype "passive"))
      (node (ref "JP11") (pin "1") (pinfunction "1_1") (pintype "passive"))
      (node (ref "JP11") (pin "3") (pinfunction "3_3") (pintype "passive"))
      (node (ref "JP12") (pin "1") (pinfunction "1_1") (pintype "passive"))
      (node (ref "JP12") (pin "3") (pinfunction "3_3") (pintype "passive"))
      (node (ref "JP13") (pin "1") (pinfunction "1_1") (pintype "passive"))
      (node (ref "JP13") (pin "11") (pinfunction "11_11") (pintype "passive"))
      (node (ref "JP13") (pin "13") (pinfunction "13_13") (pintype "passive"))
      (node (ref "JP13") (pin "15") (pinfunction "15_15") (pintype "passive"))
      (node (ref "JP13") (pin "17") (pinfunction "17_17") (pintype "passive"))
      (node (ref "JP13") (pin "19") (pinfunction "19_19") (pintype "passive"))
      (node (ref "JP13") (pin "21") (pinfunction "21_21") (pintype "passive"))
      (node (ref "JP13") (pin "23") (pinfunction "23_23") (pintype "passive"))
      (node (ref "JP13") (pin "3") (pinfunction "3_3") (pintype "passive"))
      (node (ref "JP13") (pin "5") (pinfunction "5_5") (pintype "passive"))
      (node (ref "JP13") (pin "7") (pinfunction "7_7") (pintype "passive"))
      (node (ref "JP13") (pin "9") (pinfunction "9_9") (pintype "passive"))
      (node (ref "JP2") (pin "10") (pinfunction "10_10") (pintype "passive"))
      (node (ref "JP2") (pin "12") (pinfunction "12_12") (pintype "passive"))
      (node (ref "JP2") (pin "14") (pinfunction "14_14") (pintype "passive"))
      (node (ref "JP2") (pin "16") (pinfunction "16_16") (pintype "passive"))
      (node (ref "JP2") (pin "18") (pinfunction "18_18") (pintype "passive"))
      (node (ref "JP2") (pin "2") (pinfunction "2_2") (pintype "passive"))
      (node (ref "JP2") (pin "20") (pinfunction "20_20") (pintype "passive"))
      (node (ref "JP2") (pin "22") (pinfunction "22_22") (pintype "passive"))
      (node (ref "JP2") (pin "24") (pinfunction "24_24") (pintype "passive"))
      (node (ref "JP2") (pin "26") (pinfunction "26_26") (pintype "passive"))
      (node (ref "JP2") (pin "28") (pinfunction "28_28") (pintype "passive"))
      (node (ref "JP2") (pin "30") (pinfunction "30_30") (pintype "passive"))
      (node (ref "JP2") (pin "32") (pinfunction "32_32") (pintype "passive"))
      (node (ref "JP2") (pin "4") (pinfunction "4_4") (pintype "passive"))
      (node (ref "JP2") (pin "6") (pinfunction "6_6") (pintype "passive"))
      (node (ref "JP2") (pin "8") (pinfunction "8_8") (pintype "passive"))
      (node (ref "JP3") (pin "10") (pinfunction "10_10") (pintype "passive"))
      (node (ref "JP3") (pin "12") (pinfunction "12_12") (pintype "passive"))
      (node (ref "JP3") (pin "14") (pinfunction "14_14") (pintype "passive"))
      (node (ref "JP3") (pin "16") (pinfunction "16_16") (pintype "passive"))
      (node (ref "JP3") (pin "2") (pinfunction "2_2") (pintype "passive"))
      (node (ref "JP3") (pin "4") (pinfunction "4_4") (pintype "passive"))
      (node (ref "JP3") (pin "6") (pinfunction "6_6") (pintype "passive"))
      (node (ref "JP3") (pin "8") (pinfunction "8_8") (pintype "passive"))
      (node (ref "JP4") (pin "10") (pinfunction "10_10") (pintype "passive"))
      (node (ref "JP4") (pin "12") (pinfunction "12_12") (pintype "passive"))
      (node (ref "JP4") (pin "14") (pinfunction "14_14") (pintype "passive"))
      (node (ref "JP4") (pin "16") (pinfunction "16_16") (pintype "passive"))
      (node (ref "JP4") (pin "2") (pinfunction "2_2") (pintype "passive"))
      (node (ref "JP4") (pin "4") (pinfunction "4_4") (pintype "passive"))
      (node (ref "JP4") (pin "6") (pinfunction "6_6") (pintype "passive"))
      (node (ref "JP4") (pin "8") (pinfunction "8_8") (pintype "passive"))
      (node (ref "JP8") (pin "3") (pinfunction "3_3") (pintype "passive"))
      (node (ref "LED1") (pin "C") (pinfunction "C_C") (pintype "passive"))
      (node (ref "LED2") (pin "C") (pinfunction "C_C") (pintype "passive"))
      (node (ref "LED3") (pin "C") (pinfunction "C_C") (pintype "passive"))
      (node (ref "LED4") (pin "C") (pinfunction "C_C") (pintype "passive"))
      (node (ref "LED5") (pin "C") (pinfunction "C_C") (pintype "passive"))
      (node (ref "PL1") (pin "15") (pinfunction "S_15") (pintype "passive"))
      (node (ref "PL1") (pin "17") (pinfunction "S_17") (pintype "passive"))
      (node (ref "PL1") (pin "18") (pinfunction "S_18") (pintype "passive"))
      (node (ref "PL1") (pin "19") (pinfunction "S_19") (pintype "passive"))
      (node (ref "PL1") (pin "24") (pinfunction "S_24") (pintype "passive"))
      (node (ref "PL1") (pin "3") (pinfunction "S_3") (pintype "passive"))
      (node (ref "PL1") (pin "5") (pinfunction "S_5") (pintype "passive"))
      (node (ref "PL1") (pin "7") (pinfunction "S_7") (pintype "passive"))
      (node (ref "S1") (pin "3") (pinfunction "3_3") (pintype "passive"))
      (node (ref "S2") (pin "3") (pinfunction "P_3") (pintype "passive"))
      (node (ref "S2") (pin "4") (pinfunction "P1_4") (pintype "passive"))
      (node (ref "S8") (pin "1") (pinfunction "S_1") (pintype "passive"))
      (node (ref "S8") (pin "2") (pinfunction "S1_2") (pintype "passive"))
      (node (ref "SV1") (pin "14") (pinfunction "14_14") (pintype "passive"))
      (node (ref "SV1") (pin "20") (pinfunction "20_20") (pintype "passive"))
      (node (ref "SV1") (pin "25") (pinfunction "25_25") (pintype "passive"))
      (node (ref "SV1") (pin "30") (pinfunction "30_30") (pintype "passive"))
      (node (ref "SV1") (pin "34") (pinfunction "34_34") (pintype "passive"))
      (node (ref "SV1") (pin "39") (pinfunction "39_39") (pintype "passive"))
      (node (ref "SV1") (pin "6") (pinfunction "6_6") (pintype "passive"))
      (node (ref "SV1") (pin "9") (pinfunction "9_9") (pintype "passive"))
      (node (ref "U$1") (pin "GND1") (pinfunction "GND1_GND1") (pintype "bidirectional"))
      (node (ref "U$1") (pin "GND3") (pinfunction "GND3_GND3") (pintype "bidirectional"))
      (node (ref "U$1") (pin "GND6") (pinfunction "GND6_GND6") (pintype "bidirectional"))
      (node (ref "U18") (pin "15") (pinfunction "REF_IN(-)_15") (pintype "passive"))
      (node (ref "U18") (pin "24") (pinfunction "DGND_24") (pintype "passive"))
      (node (ref "U18") (pin "4") (pinfunction "POL_4") (pintype "passive"))
      (node (ref "U18") (pin "8") (pinfunction "AGND_8") (pintype "passive"))
      (node (ref "U19") (pin "19") (pinfunction "SIGGND1_19") (pintype "passive"))
      (node (ref "U19") (pin "38") (pinfunction "SIGGND0_38") (pintype "passive"))
      (node (ref "U19") (pin "4") (pinfunction "*BIN/2SCOMP_4") (pintype "passive"))
      (node (ref "U19") (pin "43") (pinfunction "DGND_2_43") (pintype "passive"))
      (node (ref "U19") (pin "51") (pinfunction "DGND_51") (pintype "passive"))
      (node (ref "U19") (pin "52") (pinfunction "AGND_52") (pintype "passive"))
      (node (ref "U2") (pin "10") (pinfunction "10_10") (pintype "passive"))
      (node (ref "U2") (pin "12") (pinfunction "12_12") (pintype "passive"))
      (node (ref "U2") (pin "14") (pinfunction "14_14") (pintype "passive"))
      (node (ref "U2") (pin "16") (pinfunction "16_16") (pintype "passive"))
      (node (ref "U2") (pin "18") (pinfunction "18_18") (pintype "passive"))
      (node (ref "U2") (pin "2") (pinfunction "2_2") (pintype "passive"))
      (node (ref "U2") (pin "20") (pinfunction "20_20") (pintype "passive"))
      (node (ref "U2") (pin "22") (pinfunction "22_22") (pintype "passive"))
      (node (ref "U2") (pin "24") (pinfunction "24_24") (pintype "passive"))
      (node (ref "U2") (pin "26") (pinfunction "26_26") (pintype "passive"))
      (node (ref "U2") (pin "28") (pinfunction "28_28") (pintype "passive"))
      (node (ref "U2") (pin "30") (pinfunction "30_30") (pintype "passive"))
      (node (ref "U2") (pin "32") (pinfunction "32_32") (pintype "passive"))
      (node (ref "U2") (pin "4") (pinfunction "4_4") (pintype "passive"))
      (node (ref "U2") (pin "6") (pinfunction "6_6") (pintype "passive"))
      (node (ref "U2") (pin "8") (pinfunction "8_8") (pintype "passive"))
      (node (ref "U20") (pin "4") (pinfunction "GND_4") (pintype "passive"))
      (node (ref "U21") (pin "15") (pinfunction "REF_IN(-)_15") (pintype "passive"))
      (node (ref "U21") (pin "24") (pinfunction "DGND_24") (pintype "passive"))
      (node (ref "U21") (pin "4") (pinfunction "POL_4") (pintype "passive"))
      (node (ref "U21") (pin "8") (pinfunction "AGND_8") (pintype "passive"))
      (node (ref "U23") (pin "15") (pinfunction "REF_IN(-)_15") (pintype "passive"))
      (node (ref "U23") (pin "24") (pinfunction "DGND_24") (pintype "passive"))
      (node (ref "U23") (pin "4") (pinfunction "POL_4") (pintype "passive"))
      (node (ref "U23") (pin "8") (pinfunction "AGND_8") (pintype "passive"))
      (node (ref "U24") (pin "15") (pinfunction "REF_IN(-)_15") (pintype "passive"))
      (node (ref "U24") (pin "24") (pinfunction "DGND_24") (pintype "passive"))
      (node (ref "U24") (pin "4") (pinfunction "POL_4") (pintype "passive"))
      (node (ref "U24") (pin "8") (pinfunction "AGND_8") (pintype "passive"))
      (node (ref "U25") (pin "15") (pinfunction "REF_IN(-)_15") (pintype "passive"))
      (node (ref "U25") (pin "24") (pinfunction "DGND_24") (pintype "passive"))
      (node (ref "U25") (pin "4") (pinfunction "POL_4") (pintype "passive"))
      (node (ref "U25") (pin "8") (pinfunction "AGND_8") (pintype "passive"))
      (node (ref "U26") (pin "15") (pinfunction "REF_IN(-)_15") (pintype "passive"))
      (node (ref "U26") (pin "24") (pinfunction "DGND_24") (pintype "passive"))
      (node (ref "U26") (pin "4") (pinfunction "POL_4") (pintype "passive"))
      (node (ref "U26") (pin "8") (pinfunction "AGND_8") (pintype "passive"))
      (node (ref "U27") (pin "15") (pinfunction "REF_IN(-)_15") (pintype "passive"))
      (node (ref "U27") (pin "24") (pinfunction "DGND_24") (pintype "passive"))
      (node (ref "U27") (pin "4") (pinfunction "POL_4") (pintype "passive"))
      (node (ref "U27") (pin "8") (pinfunction "AGND_8") (pintype "passive"))
      (node (ref "U28") (pin "15") (pinfunction "REF_IN(-)_15") (pintype "passive"))
      (node (ref "U28") (pin "24") (pinfunction "DGND_24") (pintype "passive"))
      (node (ref "U28") (pin "4") (pinfunction "POL_4") (pintype "passive"))
      (node (ref "U28") (pin "8") (pinfunction "AGND_8") (pintype "passive"))
      (node (ref "U4") (pin "4") (pinfunction "GND_4") (pintype "passive"))
      (node (ref "U5") (pin "1") (pinfunction "V4BGND_1") (pintype "passive"))
      (node (ref "U5") (pin "10") (pinfunction "V7BGND_10") (pintype "passive"))
      (node (ref "U5") (pin "11") (pinfunction "V7AGND_11") (pintype "passive"))
      (node (ref "U5") (pin "13") (pinfunction "V6AGND_13") (pintype "passive"))
      (node (ref "U5") (pin "16") (pinfunction "AGND_4_16") (pintype "passive"))
      (node (ref "U5") (pin "18") (pinfunction "V5AGND_18") (pintype "passive"))
      (node (ref "U5") (pin "20") (pinfunction "V4AGND_20") (pintype "passive"))
      (node (ref "U5") (pin "21") (pinfunction "V3AGND_21") (pintype "passive"))
      (node (ref "U5") (pin "23") (pinfunction "V2AGND_23") (pintype "passive"))
      (node (ref "U5") (pin "25") (pinfunction "V1AGND_25") (pintype "passive"))
      (node (ref "U5") (pin "27") (pinfunction "V0AGND_27") (pintype "passive"))
      (node (ref "U5") (pin "29") (pinfunction "AGND_29") (pintype "passive"))
      (node (ref "U5") (pin "3") (pinfunction "V5BGND_3") (pintype "passive"))
      (node (ref "U5") (pin "32") (pinfunction "REFGND_32") (pintype "passive"))
      (node (ref "U5") (pin "34") (pinfunction "REFINOUTGND_34") (pintype "passive"))
      (node (ref "U5") (pin "35") (pinfunction "REFSEL_35") (pintype "passive"))
      (node (ref "U5") (pin "37") (pinfunction "SEQEN_37") (pintype "passive"))
      (node (ref "U5") (pin "38") (pinfunction "HW_RNGSEL1_38") (pintype "passive"))
      (node (ref "U5") (pin "39") (pinfunction "HW_RNGSEL0_39") (pintype "passive"))
      (node (ref "U5") (pin "41") (pinfunction "DB0_41") (pintype "passive"))
      (node (ref "U5") (pin "42") (pinfunction "DB1_42") (pintype "passive"))
      (node (ref "U5") (pin "43") (pinfunction "DB2_43") (pintype "passive"))
      (node (ref "U5") (pin "44") (pinfunction "DB3_44") (pintype "passive"))
      (node (ref "U5") (pin "45") (pinfunction "DB4/*SER1W_45") (pintype "passive"))
      (node (ref "U5") (pin "46") (pinfunction "DB5/CRCEN_46") (pintype "passive"))
      (node (ref "U5") (pin "47") (pinfunction "DB6_47") (pintype "passive"))
      (node (ref "U5") (pin "48") (pinfunction "DB7_48") (pintype "passive"))
      (node (ref "U5") (pin "5") (pinfunction "AGND_2_5") (pintype "passive"))
      (node (ref "U5") (pin "50") (pinfunction "DGND_50") (pintype "passive"))
      (node (ref "U5") (pin "51") (pinfunction "REGGNDD_51") (pintype "passive"))
      (node (ref "U5") (pin "53") (pinfunction "DB8_53") (pintype "passive"))
      (node (ref "U5") (pin "54") (pinfunction "DB9_54") (pintype "passive"))
      (node (ref "U5") (pin "58") (pinfunction "DB13/OS0_58") (pintype "passive"))
      (node (ref "U5") (pin "59") (pinfunction "DB14/OS1_59") (pintype "passive"))
      (node (ref "U5") (pin "60") (pinfunction "DB15/OS2_60") (pintype "passive"))
      (node (ref "U5") (pin "61") (pinfunction "*WR/BURST_61") (pintype "passive"))
      (node (ref "U5") (pin "64") (pinfunction "CHSEL0_64") (pintype "passive"))
      (node (ref "U5") (pin "65") (pinfunction "CHSEL1_65") (pintype "passive"))
      (node (ref "U5") (pin "66") (pinfunction "CHSEL2_66") (pintype "passive"))
      (node (ref "U5") (pin "69") (pinfunction "REGGND_69") (pintype "passive"))
      (node (ref "U5") (pin "72") (pinfunction "AGND_3_72") (pintype "passive"))
      (node (ref "U5") (pin "74") (pinfunction "V0BGND_74") (pintype "passive"))
      (node (ref "U5") (pin "76") (pinfunction "V1BGND_76") (pintype "passive"))
      (node (ref "U5") (pin "78") (pinfunction "V2BGND_78") (pintype "passive"))
      (node (ref "U5") (pin "8") (pinfunction "V6BGND_8") (pintype "passive"))
      (node (ref "U5") (pin "80") (pinfunction "V3BGND_80") (pintype "passive"))
      (node (ref "X1") (pin "3") (pinfunction "S_3") (pintype "passive"))
      (node (ref "Y1") (pin "2") (pinfunction "GND_2") (pintype "bidirectional"))
      (node (ref "Y3") (pin "2") (pinfunction "GND_2") (pintype "bidirectional"))
    )
    (net (code "100") (name "HB_CURR_LIM") (class "Default")
      (node (ref "LED1") (pin "A") (pinfunction "A_A") (pintype "passive"))
      (node (ref "R11") (pin "1") (pinfunction "1_1") (pintype "passive"))
    )
    (net (code "101") (name "HEARTBEAT") (class "Default")
      (node (ref "R11") (pin "2") (pinfunction "2_2") (pintype "passive"))
      (node (ref "SV1") (pin "3") (pinfunction "3_3") (pintype "passive"))
      (node (ref "U$1") (pin "6-OUT1D") (pinfunction "6-OUT1D_6-OUT1D") (pintype "bidirectional"))
    )
    (net (code "102") (name "LC_1_CS0") (class "Default")
      (node (ref "SV1") (pin "29") (pinfunction "29_29") (pintype "passive"))
      (node (ref "U$1") (pin "41-A17/MISO1") (pinfunction "41-A17/MISO1_41-A17/MISO1") (pintype "bidirectional"))
      (node (ref "U18") (pin "19") (pinfunction "*CS_19") (pintype "passive"))
    )
    (net (code "103") (name "LC_1_CS1") (class "Default")
      (node (ref "SV1") (pin "26") (pinfunction "26_26") (pintype "passive"))
      (node (ref "U$1") (pin "14-A0/TX3/SPDIF_OUT") (pinfunction "14-A0/TX3/SPDIF_OUT_14-A0/TX3/SPDIF_OUT") (pintype "bidirectional"))
      (node (ref "U21") (pin "19") (pinfunction "*CS_19") (pintype "passive"))
    )
    (net (code "104") (name "LC_1_CS2") (class "Default")
      (node (ref "SV1") (pin "24") (pinfunction "24_24") (pintype "passive"))
      (node (ref "U$1") (pin "15-A1/RX3/SPDIF_IN") (pinfunction "15-A1/RX3/SPDIF_IN_15-A1/RX3/SPDIF_IN") (pintype "bidirectional"))
      (node (ref "U23") (pin "19") (pinfunction "*CS_19") (pintype "passive"))
    )
    (net (code "105") (name "LC_1_CS3") (class "Default")
      (node (ref "SV1") (pin "22") (pinfunction "22_22") (pintype "passive"))
      (node (ref "U$1") (pin "16-A2/RX4/SCL1") (pinfunction "16-A2/RX4/SCL1_16-A2/RX4/SCL1") (pintype "bidirectional"))
      (node (ref "U24") (pin "19") (pinfunction "*CS_19") (pintype "passive"))
    )
    (net (code "106") (name "LC_1_CS4") (class "Default")
      (node (ref "SV1") (pin "40") (pinfunction "40_40") (pintype "passive"))
      (node (ref "U$1") (pin "33-MCLK2") (pinfunction "33-MCLK2_33-MCLK2") (pintype "bidirectional"))
      (node (ref "U25") (pin "19") (pinfunction "*CS_19") (pintype "passive"))
    )
    (net (code "107") (name "LC_1_CS5") (class "Default")
      (node (ref "SV1") (pin "38") (pinfunction "38_38") (pintype "passive"))
      (node (ref "U$1") (pin "34-RX8") (pinfunction "34-RX8_34-RX8") (pintype "bidirectional"))
      (node (ref "U26") (pin "19") (pinfunction "*CS_19") (pintype "passive"))
    )
    (net (code "108") (name "LC_1_CS6") (class "Default")
      (node (ref "SV1") (pin "37") (pinfunction "37_37") (pintype "passive"))
      (node (ref "U$1") (pin "35-TX8") (pinfunction "35/TX8_35-TX8") (pintype "bidirectional"))
      (node (ref "U27") (pin "19") (pinfunction "*CS_19") (pintype "passive"))
    )
    (net (code "109") (name "LC_1_CS7") (class "Default")
      (node (ref "SV1") (pin "36") (pinfunction "36_36") (pintype "passive"))
      (node (ref "U$1") (pin "36-PWM") (pinfunction "36-PWM_36-PWM") (pintype "bidirectional"))
      (node (ref "U28") (pin "19") (pinfunction "*CS_19") (pintype "passive"))
    )
    (net (code "110") (name "LC_1_MCLK") (class "Default")
      (node (ref "U18") (pin "2") (pinfunction "MCLK_IN_2") (pintype "passive"))
      (node (ref "Y3") (pin "3") (pinfunction "OUT_3") (pintype "bidirectional"))
    )
    (net (code "111") (name "LC_1_RDY0") (class "Default")
      (node (ref "SV1") (pin "13") (pinfunction "13_13") (pintype "passive"))
      (node (ref "U$1") (pin "20-A6/TX5/LRCLK1") (pinfunction "20-A6/TX5/LRCLK1_20-A6/TX5/LRCLK1") (pintype "bidirectional"))
      (node (ref "U18") (pin "20") (pinfunction "*RDY_20") (pintype "passive"))
    )
    (net (code "112") (name "LC_1_RDY1") (class "Default")
      (node (ref "SV1") (pin "15") (pinfunction "15_15") (pintype "passive"))
      (node (ref "U$1") (pin "19-A5/SCL0") (pinfunction "19-A5/SCL0_19-A5/SCL0") (pintype "bidirectional"))
      (node (ref "U21") (pin "20") (pinfunction "*RDY_20") (pintype "passive"))
    )
    (net (code "113") (name "LC_1_RDY2") (class "Default")
      (node (ref "SV1") (pin "16") (pinfunction "16_16") (pintype "passive"))
      (node (ref "U$1") (pin "18-A4/SDA0") (pinfunction "18-A4/SDA0_18-A4/SDA0") (pintype "bidirectional"))
      (node (ref "U23") (pin "20") (pinfunction "*RDY_20") (pintype "passive"))
    )
    (net (code "114") (name "LC_1_RDY3") (class "Default")
      (node (ref "SV1") (pin "18") (pinfunction "18_18") (pintype "passive"))
      (node (ref "U$1") (pin "17-A3/TX4/SDA1") (pinfunction "17-A3/TX4/SDA1_17-A3/TX4/SDA1") (pintype "bidirectional"))
      (node (ref "U24") (pin "20") (pinfunction "*RDY_20") (pintype "passive"))
    )
    (net (code "115") (name "LC_1_RDY4") (class "Default")
      (node (ref "SV1") (pin "31") (pinfunction "31_31") (pintype "passive"))
      (node (ref "U$1") (pin "40-A16/CS1") (pinfunction "40-A16/CS1_40-A16/CS1") (pintype "bidirectional"))
      (node (ref "U25") (pin "20") (pinfunction "*RDY_20") (pintype "passive"))
    )
    (net (code "116") (name "LC_1_RDY5") (class "Default")
      (node (ref "SV1") (pin "32") (pinfunction "32_32") (pintype "passive"))
      (node (ref "U$1") (pin "39-A15/CS/OUT1A") (pinfunction "39-A15/CS/OUT1A_39-A15/CS/OUT1A") (pintype "bidirectional"))
      (node (ref "U26") (pin "20") (pinfunction "*RDY_20") (pintype "passive"))
    )
    (net (code "117") (name "LC_1_RDY6") (class "Default")
      (node (ref "SV1") (pin "33") (pinfunction "33_33") (pintype "passive"))
      (node (ref "U$1") (pin "38-A14/CS/IN1") (pinfunction "38-A14/CS/IN1_38-A14/CS/IN1") (pintype "bidirectional"))
      (node (ref "U27") (pin "20") (pinfunction "*RDY_20") (pintype "passive"))
    )
    (net (code "118") (name "LC_1_RDY7") (class "Default")
      (node (ref "SV1") (pin "35") (pinfunction "35_35") (pintype "passive"))
      (node (ref "U$1") (pin "37-PWM") (pinfunction "37-PWM_37-PWM") (pintype "bidirectional"))
      (node (ref "U28") (pin "20") (pinfunction "*RDY_20") (pintype "passive"))
    )
    (net (code "119") (name "LDAC") (class "Default")
      (node (ref "SV1") (pin "11") (pinfunction "11_11") (pintype "passive"))
      (node (ref "U$1") (pin "4-BCLK2") (pinfunction "4-BCLK2_4-BCLK2") (pintype "bidirectional"))
      (node (ref "U19") (pin "1") (pinfunction "*LDAC_1") (pintype "passive"))
    )
    (net (code "120") (name "MISO") (class "Default")
      (node (ref "SV1") (pin "21") (pinfunction "21_21") (pintype "passive"))
      (node (ref "U$1") (pin "12-MISO/MQSL") (pinfunction "12-MISO/MQSL_12-MISO/MQSL") (pintype "bidirectional"))
      (node (ref "U18") (pin "21") (pinfunction "DOUT_21") (pintype "passive"))
      (node (ref "U19") (pin "49") (pinfunction "SDO_49") (pintype "passive"))
      (node (ref "U21") (pin "21") (pinfunction "DOUT_21") (pintype "passive"))
      (node (ref "U23") (pin "21") (pinfunction "DOUT_21") (pintype "passive"))
      (node (ref "U24") (pin "21") (pinfunction "DOUT_21") (pintype "passive"))
      (node (ref "U25") (pin "21") (pinfunction "DOUT_21") (pintype "passive"))
      (node (ref "U26") (pin "21") (pinfunction "DOUT_21") (pintype "passive"))
      (node (ref "U27") (pin "21") (pinfunction "DOUT_21") (pintype "passive"))
      (node (ref "U28") (pin "21") (pinfunction "DOUT_21") (pintype "passive"))
      (node (ref "U5") (pin "57") (pinfunction "DB12/SDOA_57") (pintype "passive"))
    )
    (net (code "121") (name "MOSI") (class "Default")
      (node (ref "SV1") (pin "19") (pinfunction "19_19") (pintype "passive"))
      (node (ref "U$1") (pin "11-MOSI/CTX1") (pinfunction "11-MOSI/CTX1_11-MOSI/CTX1") (pintype "bidirectional"))
      (node (ref "U18") (pin "22") (pinfunction "DIN_22") (pintype "passive"))
      (node (ref "U19") (pin "47") (pinfunction "SDI_47") (pintype "passive"))
      (node (ref "U21") (pin "22") (pinfunction "DIN_22") (pintype "passive"))
      (node (ref "U23") (pin "22") (pinfunction "DIN_22") (pintype "passive"))
      (node (ref "U24") (pin "22") (pinfunction "DIN_22") (pintype "passive"))
      (node (ref "U25") (pin "22") (pinfunction "DIN_22") (pintype "passive"))
      (node (ref "U26") (pin "22") (pinfunction "DIN_22") (pintype "passive"))
      (node (ref "U27") (pin "22") (pinfunction "DIN_22") (pintype "passive"))
      (node (ref "U28") (pin "22") (pinfunction "DIN_22") (pintype "passive"))
      (node (ref "U5") (pin "55") (pinfunction "DB10/SDI_55") (pintype "passive"))
    )
    (net (code "122") (name "N$12") (class "Default")
      (node (ref "SV1") (pin "28") (pinfunction "28_28") (pintype "passive"))
    )
    (net (code "123") (name "N$13") (class "Default")
      (node (ref "SV1") (pin "27") (pinfunction "27_27") (pintype "passive"))
    )
    (net (code "124") (name "PG_CURR_LIM") (class "Default")
      (node (ref "LED4") (pin "A") (pinfunction "A_A") (pintype "passive"))
      (node (ref "R1") (pin "1") (pinfunction "1_1") (pintype "passive"))
    )
    (net (code "125") (name "PG_SIG") (class "Default")
      (node (ref "Q1") (pin "B") (pinfunction "B_B") (pintype "passive"))
      (node (ref "R12") (pin "1") (pinfunction "1_1") (pintype "passive"))
    )
    (net (code "126") (name "POWER_GOOD") (class "Default")
      (node (ref "PL1") (pin "8") (pinfunction "S_8") (pintype "passive"))
      (node (ref "R12") (pin "2") (pinfunction "2_2") (pintype "passive"))
    )
    (net (code "127") (name "POWER_GOOD_SUPP") (class "Default")
      (node (ref "Q1") (pin "E") (pinfunction "E_E") (pintype "passive"))
      (node (ref "R1") (pin "2") (pinfunction "2_2") (pintype "passive"))
    )
    (net (code "128") (name "PSU_ENABLE") (class "Default")
      (node (ref "PL1") (pin "16") (pinfunction "S_16") (pintype "passive"))
      (node (ref "S1") (pin "2") (pinfunction "2_2") (pintype "passive"))
    )
    (net (code "129") (name "PWR") (class "Default")
      (node (ref "C15") (pin "+") (pinfunction "+_+") (pintype "passive"))
      (node (ref "JP9") (pin "1") (pinfunction "1_1") (pintype "passive"))
      (node (ref "SV1") (pin "2") (pinfunction "2_2") (pintype "passive"))
      (node (ref "SV1") (pin "4") (pinfunction "4_4") (pintype "passive"))
      (node (ref "U$1") (pin "VIN") (pinfunction "VIN_VIN") (pintype "bidirectional"))
    )
    (net (code "130") (name "RX") (class "Default")
      (node (ref "JP8") (pin "2") (pinfunction "2_2") (pintype "passive"))
      (node (ref "SV1") (pin "10") (pinfunction "10_10") (pintype "passive"))
      (node (ref "U$1") (pin "0-RX1/CS1/CRX2") (pinfunction "0-RX1/CS1/CRX2_0-RX1/CS1/CRX2") (pintype "bidirectional"))
    )
    (net (code "131") (name "SCLK") (class "Default")
      (node (ref "SV1") (pin "23") (pinfunction "23_23") (pintype "passive"))
      (node (ref "U$1") (pin "13-SCK/LED") (pinfunction "13-SCK/LED_13-SCK/LED") (pintype "bidirectional"))
      (node (ref "U18") (pin "1") (pinfunction "SCLK_1") (pintype "passive"))
      (node (ref "U19") (pin "46") (pinfunction "SCLK_46") (pintype "passive"))
      (node (ref "U21") (pin "1") (pinfunction "SCLK_1") (pintype "passive"))
      (node (ref "U23") (pin "1") (pinfunction "SCLK_1") (pintype "passive"))
      (node (ref "U24") (pin "1") (pinfunction "SCLK_1") (pintype "passive"))
      (node (ref "U25") (pin "1") (pinfunction "SCLK_1") (pintype "passive"))
      (node (ref "U26") (pin "1") (pinfunction "SCLK_1") (pintype "passive"))
      (node (ref "U27") (pin "1") (pinfunction "SCLK_1") (pintype "passive"))
      (node (ref "U28") (pin "1") (pinfunction "SCLK_1") (pintype "passive"))
      (node (ref "U5") (pin "62") (pinfunction "SCLK/*RD_62") (pintype "passive"))
    )
    (net (code "132") (name "SS_ADC_2") (class "Default")
      (node (ref "SV1") (pin "7") (pinfunction "7_7") (pintype "passive"))
      (node (ref "U$1") (pin "3-LRCLK2") (pinfunction "3-LRCLK2_3-LRCLK2") (pintype "bidirectional"))
      (node (ref "U5") (pin "63") (pinfunction "*CS_63") (pintype "passive"))
    )
    (net (code "133") (name "SS_DAC_2") (class "Default")
      (node (ref "SV1") (pin "12") (pinfunction "12_12") (pintype "passive"))
      (node (ref "U$1") (pin "5-IN2") (pinfunction "5-IN2_5-IN2") (pintype "bidirectional"))
      (node (ref "U19") (pin "45") (pinfunction "*SYNC_45") (pintype "passive"))
    )
    (net (code "134") (name "TX") (class "Default")
      (node (ref "JP8") (pin "1") (pinfunction "1_1") (pintype "passive"))
      (node (ref "SV1") (pin "8") (pinfunction "8_8") (pintype "passive"))
      (node (ref "U$1") (pin "1-TX1/MISO1/CTX2") (pinfunction "1-TX1/MISO1/CTX2_1-TX1/MISO1/CTX2") (pintype "bidirectional"))
    )
    (net (code "135") (name "VDD") (class "Default")
      (node (ref "C12") (pin "+") (pinfunction "+_+") (pintype "passive"))
      (node (ref "C141") (pin "1") (pinfunction "1_1") (pintype "passive"))
      (node (ref "C143") (pin "1") (pinfunction "1_1") (pintype "passive"))
      (node (ref "C148") (pin "1") (pinfunction "1_1") (pintype "passive"))
      (node (ref "C23") (pin "+") (pinfunction "+_+") (pintype "passive"))
      (node (ref "C24") (pin "+") (pinfunction "+_+") (pintype "passive"))
      (node (ref "C27") (pin "+") (pinfunction "+_+") (pintype "passive"))
      (node (ref "C33") (pin "1") (pinfunction "1_1") (pintype "passive"))
      (node (ref "C8") (pin "+") (pinfunction "+_+") (pintype "passive"))
      (node (ref "C9") (pin "+") (pinfunction "+_+") (pintype "passive"))
      (node (ref "J17") (pin "1") (pinfunction "1_1") (pintype "input"))
      (node (ref "J18") (pin "1") (pinfunction "1_1") (pintype "input"))
      (node (ref "J19") (pin "1") (pinfunction "1_1") (pintype "input"))
      (node (ref "J20") (pin "1") (pinfunction "1_1") (pintype "input"))
      (node (ref "J21") (pin "1") (pinfunction "1_1") (pintype "input"))
      (node (ref "J22") (pin "1") (pinfunction "1_1") (pintype "input"))
      (node (ref "J23") (pin "1") (pinfunction "1_1") (pintype "input"))
      (node (ref "J24") (pin "1") (pinfunction "1_1") (pintype "input"))
      (node (ref "J25") (pin "1") (pinfunction "1_1") (pintype "input"))
      (node (ref "J26") (pin "1") (pinfunction "1_1") (pintype "input"))
      (node (ref "J27") (pin "1") (pinfunction "1_1") (pintype "input"))
      (node (ref "J28") (pin "1") (pinfunction "1_1") (pintype "input"))
      (node (ref "J29") (pin "1") (pinfunction "1_1") (pintype "input"))
      (node (ref "J30") (pin "1") (pinfunction "1_1") (pintype "input"))
      (node (ref "J31") (pin "1") (pinfunction "1_1") (pintype "input"))
      (node (ref "J32") (pin "1") (pinfunction "1_1") (pintype "input"))
      (node (ref "PL1") (pin "11") (pinfunction "S_11") (pintype "passive"))
      (node (ref "R10") (pin "2") (pinfunction "2_2") (pintype "passive"))
      (node (ref "U19") (pin "11") (pinfunction "VDD_11") (pintype "passive"))
      (node (ref "U19") (pin "28") (pinfunction "VDD_2_28") (pintype "passive"))
      (node (ref "U20") (pin "2") (pinfunction "VIN_2") (pintype "passive"))
      (node (ref "U4") (pin "2") (pinfunction "VIN_2") (pintype "passive"))
      (node (ref "X1") (pin "2") (pinfunction "S_2") (pintype "passive"))
    )
    (net (code "136") (name "VDD_CURR_LIM") (class "Default")
      (node (ref "LED5") (pin "A") (pinfunction "A_A") (pintype "passive"))
      (node (ref "R10") (pin "1") (pinfunction "1_1") (pintype "passive"))
    )
    (net (code "137") (name "VREF_2") (class "Default")
      (node (ref "C10") (pin "+") (pinfunction "+_+") (pintype "passive"))
      (node (ref "C150") (pin "1") (pinfunction "1_1") (pintype "passive"))
      (node (ref "C151") (pin "1") (pinfunction "1_1") (pintype "passive"))
      (node (ref "U19") (pin "13") (pinfunction "VREF1_13") (pintype "passive"))
      (node (ref "U19") (pin "31") (pinfunction "VREF0_31") (pintype "passive"))
      (node (ref "U20") (pin "6") (pinfunction "VOUT_6") (pintype "passive"))
    )
    (net (code "138") (name "VSS") (class "Default")
      (node (ref "C145") (pin "1") (pinfunction "1_1") (pintype "passive"))
      (node (ref "C147") (pin "1") (pinfunction "1_1") (pintype "passive"))
      (node (ref "C16") (pin "-") (pinfunction "-_-") (pintype "passive"))
      (node (ref "C25") (pin "-") (pinfunction "-_-") (pintype "passive"))
      (node (ref "C26") (pin "-") (pinfunction "-_-") (pintype "passive"))
      (node (ref "PL1") (pin "14") (pinfunction "S_14") (pintype "passive"))
      (node (ref "U19") (pin "12") (pinfunction "VSS_2_12") (pintype "passive"))
      (node (ref "U19") (pin "29") (pinfunction "VSS_29") (pintype "passive"))
    )
    (net (code "139") (name "unconnected-(PL1A-S-Pad1)") (class "Default")
      (node (ref "PL1") (pin "1") (pinfunction "S_1") (pintype "passive"))
    )
    (net (code "140") (name "unconnected-(PL1B-S-Pad10)") (class "Default")
      (node (ref "PL1") (pin "10") (pinfunction "S_10") (pintype "passive"))
    )
    (net (code "141") (name "unconnected-(PL1D-S-Pad12)") (class "Default")
      (node (ref "PL1") (pin "12") (pinfunction "S_12") (pintype "passive"))
    )
    (net (code "142") (name "unconnected-(PL1E-S-Pad13)") (class "Default")
      (node (ref "PL1") (pin "13") (pinfunction "S_13") (pintype "passive"))
    )
    (net (code "143") (name "unconnected-(PL1M-S-Pad20)") (class "Default")
      (node (ref "PL1") (pin "20") (pinfunction "S_20") (pintype "passive"))
    )
    (net (code "144") (name "unconnected-(PL1N-S-Pad21)") (class "Default")
      (node (ref "PL1") (pin "21") (pinfunction "S_21") (pintype "passive"))
    )
    (net (code "145") (name "unconnected-(PL1O-S-Pad22)") (class "Default")
      (node (ref "PL1") (pin "22") (pinfunction "S_22") (pintype "passive"))
    )
    (net (code "146") (name "unconnected-(PL1S-S-Pad4)") (class "Default")
      (node (ref "PL1") (pin "4") (pinfunction "S_4") (pintype "passive"))
    )
    (net (code "147") (name "unconnected-(PL1U-S-Pad6)") (class "Default")
      (node (ref "PL1") (pin "6") (pinfunction "S_6") (pintype "passive"))
    )
    (net (code "148") (name "unconnected-(PL1X-S-Pad9)") (class "Default")
      (node (ref "PL1") (pin "9") (pinfunction "S_9") (pintype "passive"))
    )
    (net (code "149") (name "unconnected-(S1-Pad1)") (class "Default")
      (node (ref "S1") (pin "1") (pinfunction "1_1") (pintype "passive"))
    )
    (net (code "150") (name "unconnected-(S2-S1-Pad2)") (class "Default")
      (node (ref "S2") (pin "2") (pinfunction "S1_2") (pintype "passive"))
    )
    (net (code "151") (name "unconnected-(S8-P-Pad3)") (class "Default")
      (node (ref "S8") (pin "3") (pinfunction "P_3") (pintype "passive"))
    )
    (net (code "152") (name "unconnected-(SV1-Pad1)") (class "Default")
      (node (ref "SV1") (pin "1") (pinfunction "1_1") (pintype "passive"))
    )
    (net (code "153") (name "unconnected-(U$1-5V-Pad+5V)") (class "Default")
      (node (ref "U$1") (pin "+5V") (pinfunction "5V_+5V") (pintype "bidirectional"))
    )
    (net (code "154") (name "unconnected-(U$1-Pad3V3-1)") (class "Default")
      (node (ref "U$1") (pin "3V3-1") (pinfunction "3V3-1_3V3-1") (pintype "bidirectional"))
    )
    (net (code "155") (name "unconnected-(U$1-Pad3V3-2)") (class "Default")
      (node (ref "U$1") (pin "3V3-2") (pinfunction "3V3-2_3V3-2") (pintype "bidirectional"))
    )
    (net (code "156") (name "unconnected-(U$1-Pad3V3-3)") (class "Default")
      (node (ref "U$1") (pin "3V3-3") (pinfunction "3V3-3_3V3-3") (pintype "bidirectional"))
    )
    (net (code "157") (name "unconnected-(U$1-Pad21-A7{slash}RX5{slash}BCLK1)") (class "Default")
      (node (ref "U$1") (pin "21-A7/RX5/BCLK1") (pinfunction "21-A7/RX5/BCLK1_21-A7/RX5/BCLK1") (pintype "bidirectional"))
    )
    (net (code "158") (name "unconnected-(U$1-Pad22-A8{slash}CTX1)") (class "Default")
      (node (ref "U$1") (pin "22-A8/CTX1") (pinfunction "22-A8/CTX1_22-A8/CTX1") (pintype "bidirectional"))
    )
    (net (code "159") (name "unconnected-(U$1-Pad23-A9{slash}CRX1{slash}MCLK1)") (class "Default")
      (node (ref "U$1") (pin "23-A9/CRX1/MCLK1") (pinfunction "23-A9/CRX1/MCLK1_23-A9/CRX1/MCLK1") (pintype "bidirectional"))
    )
    (net (code "160") (name "unconnected-(U$1-Pad24-A10{slash}TX6{slash}SCL2)") (class "Default")
      (node (ref "U$1") (pin "24-A10/TX6/SCL2") (pinfunction "24-A10/TX6/SCL2_24-A10/TX6/SCL2") (pintype "bidirectional"))
    )
    (net (code "161") (name "unconnected-(U$1-PadD+)") (class "Default")
      (node (ref "U$1") (pin "D+") (pinfunction "D+_D+") (pintype "bidirectional"))
    )
    (net (code "162") (name "unconnected-(U$1-PadD-)") (class "Default")
      (node (ref "U$1") (pin "D-") (pinfunction "D-_D-") (pintype "bidirectional"))
    )
    (net (code "163") (name "unconnected-(U$1-PadDM)") (class "Default")
      (node (ref "U$1") (pin "DM") (pinfunction "DM_DM") (pintype "bidirectional"))
    )
    (net (code "164") (name "unconnected-(U$1-PadDP)") (class "Default")
      (node (ref "U$1") (pin "DP") (pinfunction "DP_DP") (pintype "bidirectional"))
    )
    (net (code "165") (name "unconnected-(U$1-PadG)") (class "Default")
      (node (ref "U$1") (pin "G") (pinfunction "G_G") (pintype "bidirectional"))
    )
    (net (code "166") (name "unconnected-(U$1-PadGND2)") (class "Default")
      (node (ref "U$1") (pin "GND2") (pinfunction "GND2_GND2") (pintype "bidirectional"))
    )
    (net (code "167") (name "unconnected-(U$1-PadGND4)") (class "Default")
      (node (ref "U$1") (pin "GND4") (pinfunction "GND4_GND4") (pintype "bidirectional"))
    )
    (net (code "168") (name "unconnected-(U$1-PadGND5)") (class "Default")
      (node (ref "U$1") (pin "GND5") (pinfunction "GND5_GND5") (pintype "bidirectional"))
    )
    (net (code "169") (name "unconnected-(U$1-PadLED)") (class "Default")
      (node (ref "U$1") (pin "LED") (pinfunction "LED_LED") (pintype "bidirectional"))
    )
    (net (code "170") (name "unconnected-(U$1-PadON{slash}OFF)") (class "Default")
      (node (ref "U$1") (pin "ON/OFF") (pinfunction "ON/OFF_ON/OFF") (pintype "bidirectional"))
    )
    (net (code "171") (name "unconnected-(U$1-PadPROGRAM)") (class "Default")
      (node (ref "U$1") (pin "PROGRAM") (pinfunction "PROGRAM_PROGRAM") (pintype "bidirectional"))
    )
    (net (code "172") (name "unconnected-(U$1-PadR+)") (class "Default")
      (node (ref "U$1") (pin "R+") (pinfunction "R+_R+") (pintype "bidirectional"))
    )
    (net (code "173") (name "unconnected-(U$1-PadR-)") (class "Default")
      (node (ref "U$1") (pin "R-") (pinfunction "R-_R-") (pintype "bidirectional"))
    )
    (net (code "174") (name "unconnected-(U$1-PadT+)") (class "Default")
      (node (ref "U$1") (pin "T+") (pinfunction "T+_T+") (pintype "bidirectional"))
    )
    (net (code "175") (name "unconnected-(U$1-PadT-)") (class "Default")
      (node (ref "U$1") (pin "T-") (pinfunction "T-_T-") (pintype "bidirectional"))
    )
    (net (code "176") (name "unconnected-(U$1-PadVBAT)") (class "Default")
      (node (ref "U$1") (pin "VBAT") (pinfunction "VBAT_VBAT") (pintype "bidirectional"))
    )
    (net (code "177") (name "unconnected-(U$1-PadVUSB)") (class "Default")
      (node (ref "U$1") (pin "VUSB") (pinfunction "VUSB_VUSB") (pintype "bidirectional"))
    )
    (net (code "178") (name "unconnected-(U2-Pad33)") (class "Default")
      (node (ref "U2") (pin "33") (pinfunction "33_33") (pintype "passive"))
    )
    (net (code "179") (name "unconnected-(U2-Pad34)") (class "Default")
      (node (ref "U2") (pin "34") (pinfunction "34_34") (pintype "passive"))
    )
    (net (code "180") (name "unconnected-(U4-NIC-Pad7)") (class "Default")
      (node (ref "U4") (pin "7") (pinfunction "NIC_7") (pintype "passive"))
    )
    (net (code "181") (name "unconnected-(U4-NIC_2-Pad3)") (class "Default")
      (node (ref "U4") (pin "3") (pinfunction "NIC_2_3") (pintype "passive"))
    )
    (net (code "182") (name "unconnected-(U4-TP-Pad8)") (class "Default")
      (node (ref "U4") (pin "8") (pinfunction "TP_8") (pintype "passive"))
    )
    (net (code "183") (name "unconnected-(U4-TP_2-Pad1)") (class "Default")
      (node (ref "U4") (pin "1") (pinfunction "TP_2_1") (pintype "passive"))
    )
    (net (code "184") (name "unconnected-(U4-TRIM-Pad5)") (class "Default")
      (node (ref "U4") (pin "5") (pinfunction "TRIM_5") (pintype "passive"))
    )
    (net (code "185") (name "unconnected-(U5-BUSY-Pad67)") (class "Default")
      (node (ref "U5") (pin "67") (pinfunction "BUSY_67") (pintype "passive"))
    )
    (net (code "186") (name "unconnected-(U5-DB11{slash}SDOB-Pad56)") (class "Default")
      (node (ref "U5") (pin "56") (pinfunction "DB11/SDOB_56") (pintype "passive"))
    )
    (net (code "187") (name "unconnected-(U18-*ACX-Pad17)") (class "Default")
      (node (ref "U18") (pin "17") (pinfunction "*ACX_17") (pintype "passive"))
    )
    (net (code "188") (name "unconnected-(U18-ACX-Pad16)") (class "Default")
      (node (ref "U18") (pin "16") (pinfunction "ACX_16") (pintype "passive"))
    )
    (net (code "189") (name "unconnected-(U18-VBIAS-Pad7)") (class "Default")
      (node (ref "U18") (pin "7") (pinfunction "VBIAS_7") (pintype "passive"))
    )
    (net (code "190") (name "unconnected-(U19-*BUSY-Pad5)") (class "Default")
      (node (ref "U19") (pin "5") (pinfunction "*BUSY_5") (pintype "passive"))
    )
    (net (code "191") (name "unconnected-(U19-*PEC-Pad48)") (class "Default")
      (node (ref "U19") (pin "48") (pinfunction "*PEC_48") (pintype "passive"))
    )
    (net (code "192") (name "unconnected-(U19-GPIO-Pad6)") (class "Default")
      (node (ref "U19") (pin "6") (pinfunction "GPIO_6") (pintype "passive"))
    )
    (net (code "193") (name "unconnected-(U19-MON_IN0-Pad8)") (class "Default")
      (node (ref "U19") (pin "8") (pinfunction "MON_IN0_8") (pintype "passive"))
    )
    (net (code "194") (name "unconnected-(U19-MON_IN1-Pad32)") (class "Default")
      (node (ref "U19") (pin "32") (pinfunction "MON_IN1_32") (pintype "passive"))
    )
    (net (code "195") (name "unconnected-(U19-MON_OUT-Pad7)") (class "Default")
      (node (ref "U19") (pin "7") (pinfunction "MON_OUT_7") (pintype "passive"))
    )
    (net (code "196") (name "unconnected-(U19-NC-Pad26)") (class "Default")
      (node (ref "U19") (pin "26") (pinfunction "NC_26") (pintype "passive"))
    )
    (net (code "197") (name "unconnected-(U19-NC_2-Pad27)") (class "Default")
      (node (ref "U19") (pin "27") (pinfunction "NC_2_27") (pintype "passive"))
    )
    (net (code "198") (name "unconnected-(U19-NC_3-Pad30)") (class "Default")
      (node (ref "U19") (pin "30") (pinfunction "NC_3_30") (pintype "passive"))
    )
    (net (code "199") (name "unconnected-(U19-NC_4-Pad9)") (class "Default")
      (node (ref "U19") (pin "9") (pinfunction "NC_4_9") (pintype "passive"))
    )
    (net (code "200") (name "unconnected-(U19-NC_5-Pad10)") (class "Default")
      (node (ref "U19") (pin "10") (pinfunction "NC_5_10") (pintype "passive"))
    )
    (net (code "201") (name "unconnected-(U19-NC_6-Pad14)") (class "Default")
      (node (ref "U19") (pin "14") (pinfunction "NC_6_14") (pintype "passive"))
    )
    (net (code "202") (name "unconnected-(U19-NC_7-Pad24)") (class "Default")
      (node (ref "U19") (pin "24") (pinfunction "NC_7_24") (pintype "passive"))
    )
    (net (code "203") (name "unconnected-(U19-NC_8-Pad25)") (class "Default")
      (node (ref "U19") (pin "25") (pinfunction "NC_8_25") (pintype "passive"))
    )
    (net (code "204") (name "unconnected-(U19-TEMP_OUT-Pad33)") (class "Default")
      (node (ref "U19") (pin "33") (pinfunction "TEMP_OUT_33") (pintype "passive"))
    )
    (net (code "205") (name "unconnected-(U20-NIC-Pad7)") (class "Default")
      (node (ref "U20") (pin "7") (pinfunction "NIC_7") (pintype "passive"))
    )
    (net (code "206") (name "unconnected-(U20-NIC_2-Pad3)") (class "Default")
      (node (ref "U20") (pin "3") (pinfunction "NIC_2_3") (pintype "passive"))
    )
    (net (code "207") (name "unconnected-(U20-TP-Pad8)") (class "Default")
      (node (ref "U20") (pin "8") (pinfunction "TP_8") (pintype "passive"))
    )
    (net (code "208") (name "unconnected-(U20-TP_2-Pad1)") (class "Default")
      (node (ref "U20") (pin "1") (pinfunction "TP_2_1") (pintype "passive"))
    )
    (net (code "209") (name "unconnected-(U20-TRIM-Pad5)") (class "Default")
      (node (ref "U20") (pin "5") (pinfunction "TRIM_5") (pintype "passive"))
    )
    (net (code "210") (name "unconnected-(U21-*ACX-Pad17)") (class "Default")
      (node (ref "U21") (pin "17") (pinfunction "*ACX_17") (pintype "passive"))
    )
    (net (code "211") (name "unconnected-(U21-ACX-Pad16)") (class "Default")
      (node (ref "U21") (pin "16") (pinfunction "ACX_16") (pintype "passive"))
    )
    (net (code "212") (name "unconnected-(U21-VBIAS-Pad7)") (class "Default")
      (node (ref "U21") (pin "7") (pinfunction "VBIAS_7") (pintype "passive"))
    )
    (net (code "213") (name "unconnected-(U23-*ACX-Pad17)") (class "Default")
      (node (ref "U23") (pin "17") (pinfunction "*ACX_17") (pintype "passive"))
    )
    (net (code "214") (name "unconnected-(U23-ACX-Pad16)") (class "Default")
      (node (ref "U23") (pin "16") (pinfunction "ACX_16") (pintype "passive"))
    )
    (net (code "215") (name "unconnected-(U23-VBIAS-Pad7)") (class "Default")
      (node (ref "U23") (pin "7") (pinfunction "VBIAS_7") (pintype "passive"))
    )
    (net (code "216") (name "unconnected-(U24-*ACX-Pad17)") (class "Default")
      (node (ref "U24") (pin "17") (pinfunction "*ACX_17") (pintype "passive"))
    )
    (net (code "217") (name "unconnected-(U24-ACX-Pad16)") (class "Default")
      (node (ref "U24") (pin "16") (pinfunction "ACX_16") (pintype "passive"))
    )
    (net (code "218") (name "unconnected-(U24-MCLK_OUT-Pad3)") (class "Default")
      (node (ref "U24") (pin "3") (pinfunction "MCLK_OUT_3") (pintype "passive"))
    )
    (net (code "219") (name "unconnected-(U24-VBIAS-Pad7)") (class "Default")
      (node (ref "U24") (pin "7") (pinfunction "VBIAS_7") (pintype "passive"))
    )
    (net (code "220") (name "unconnected-(U25-*ACX-Pad17)") (class "Default")
      (node (ref "U25") (pin "17") (pinfunction "*ACX_17") (pintype "passive"))
    )
    (net (code "221") (name "unconnected-(U25-ACX-Pad16)") (class "Default")
      (node (ref "U25") (pin "16") (pinfunction "ACX_16") (pintype "passive"))
    )
    (net (code "222") (name "unconnected-(U25-VBIAS-Pad7)") (class "Default")
      (node (ref "U25") (pin "7") (pinfunction "VBIAS_7") (pintype "passive"))
    )
    (net (code "223") (name "unconnected-(U26-*ACX-Pad17)") (class "Default")
      (node (ref "U26") (pin "17") (pinfunction "*ACX_17") (pintype "passive"))
    )
    (net (code "224") (name "unconnected-(U26-ACX-Pad16)") (class "Default")
      (node (ref "U26") (pin "16") (pinfunction "ACX_16") (pintype "passive"))
    )
    (net (code "225") (name "unconnected-(U26-VBIAS-Pad7)") (class "Default")
      (node (ref "U26") (pin "7") (pinfunction "VBIAS_7") (pintype "passive"))
    )
    (net (code "226") (name "unconnected-(U27-*ACX-Pad17)") (class "Default")
      (node (ref "U27") (pin "17") (pinfunction "*ACX_17") (pintype "passive"))
    )
    (net (code "227") (name "unconnected-(U27-ACX-Pad16)") (class "Default")
      (node (ref "U27") (pin "16") (pinfunction "ACX_16") (pintype "passive"))
    )
    (net (code "228") (name "unconnected-(U27-VBIAS-Pad7)") (class "Default")
      (node (ref "U27") (pin "7") (pinfunction "VBIAS_7") (pintype "passive"))
    )
    (net (code "229") (name "unconnected-(U28-*ACX-Pad17)") (class "Default")
      (node (ref "U28") (pin "17") (pinfunction "*ACX_17") (pintype "passive"))
    )
    (net (code "230") (name "unconnected-(U28-ACX-Pad16)") (class "Default")
      (node (ref "U28") (pin "16") (pinfunction "ACX_16") (pintype "passive"))
    )
    (net (code "231") (name "unconnected-(U28-MCLK_OUT-Pad3)") (class "Default")
      (node (ref "U28") (pin "3") (pinfunction "MCLK_OUT_3") (pintype "passive"))
    )
    (net (code "232") (name "unconnected-(U28-VBIAS-Pad7)") (class "Default")
      (node (ref "U28") (pin "7") (pinfunction "VBIAS_7") (pintype "passive"))
    )
    (net (code "233") (name "unconnected-(X1A-S-Pad1)") (class "Default")
      (node (ref "X1") (pin "1") (pinfunction "S_1") (pintype "passive"))
    )
    (net (code "234") (name "unconnected-(Y1-EN-Pad1)") (class "Default")
      (node (ref "Y1") (pin "1") (pinfunction "EN_1") (pintype "bidirectional"))
    )
    (net (code "235") (name "unconnected-(Y3-EN-Pad1)") (class "Default")
      (node (ref "Y3") (pin "1") (pinfunction "EN_1") (pintype "bidirectional"))
    )
  )
)
